# INV_OG5K_PW_V1.net
KiCad netlist of a schematic drawn in Altium Designer
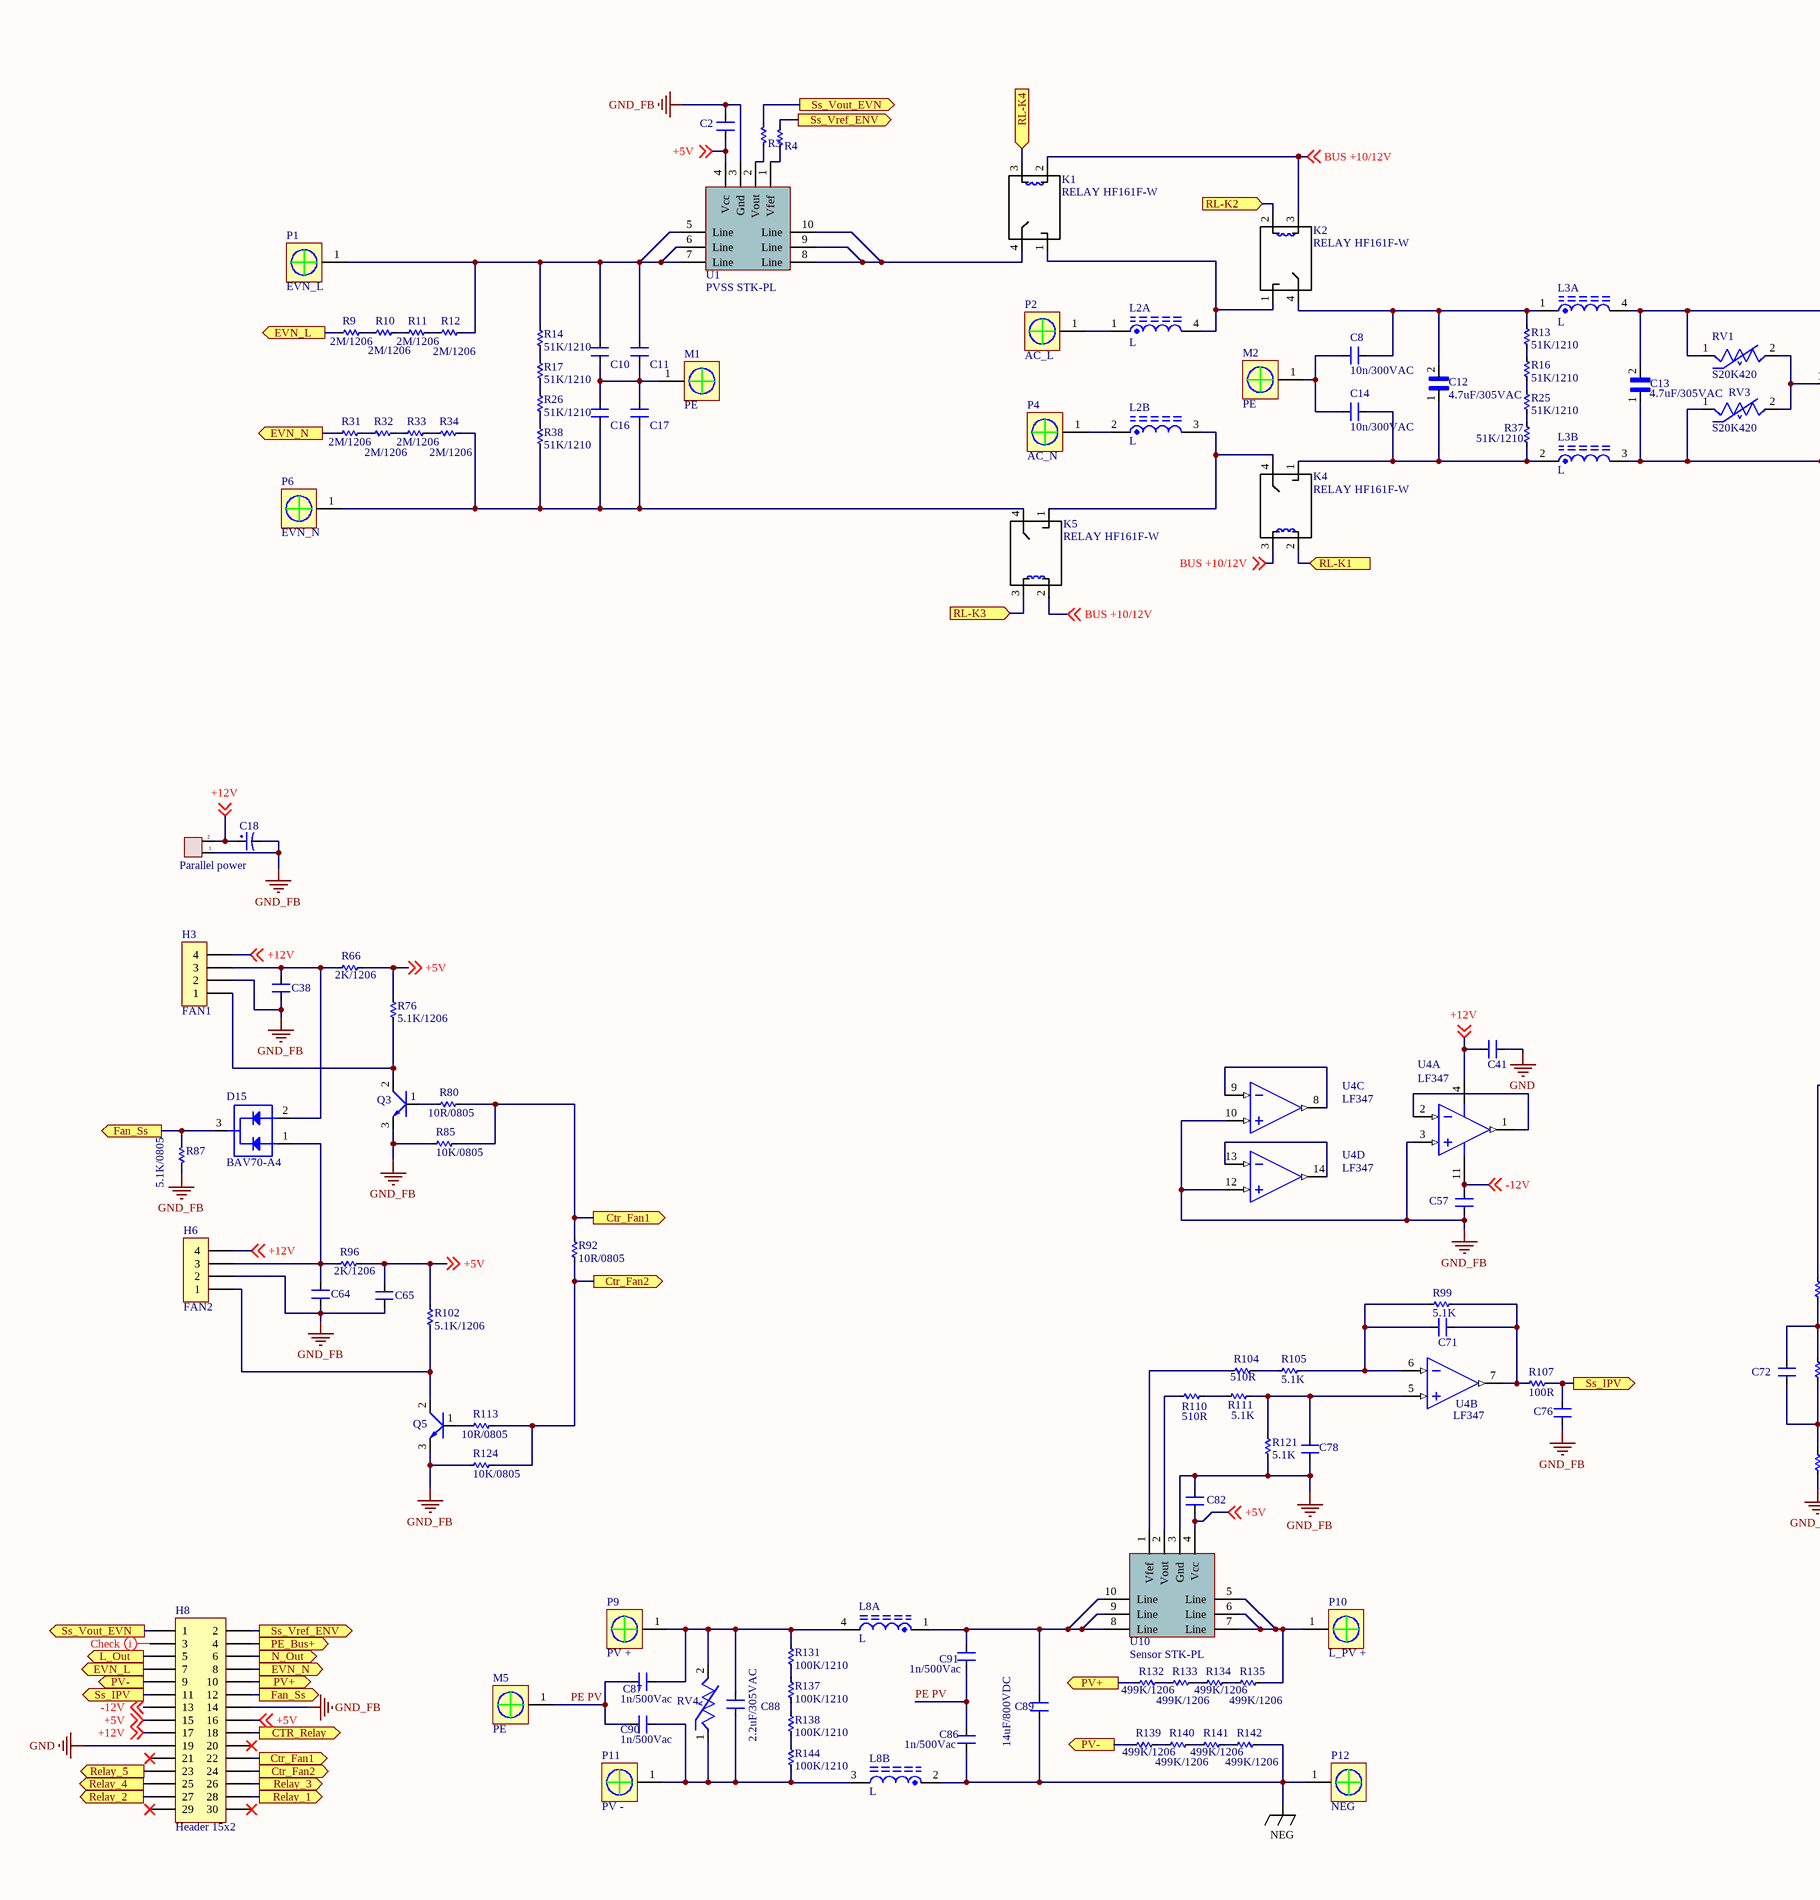
[diagram p0: INV.OG5K.PW.V1.SchDoc, left]
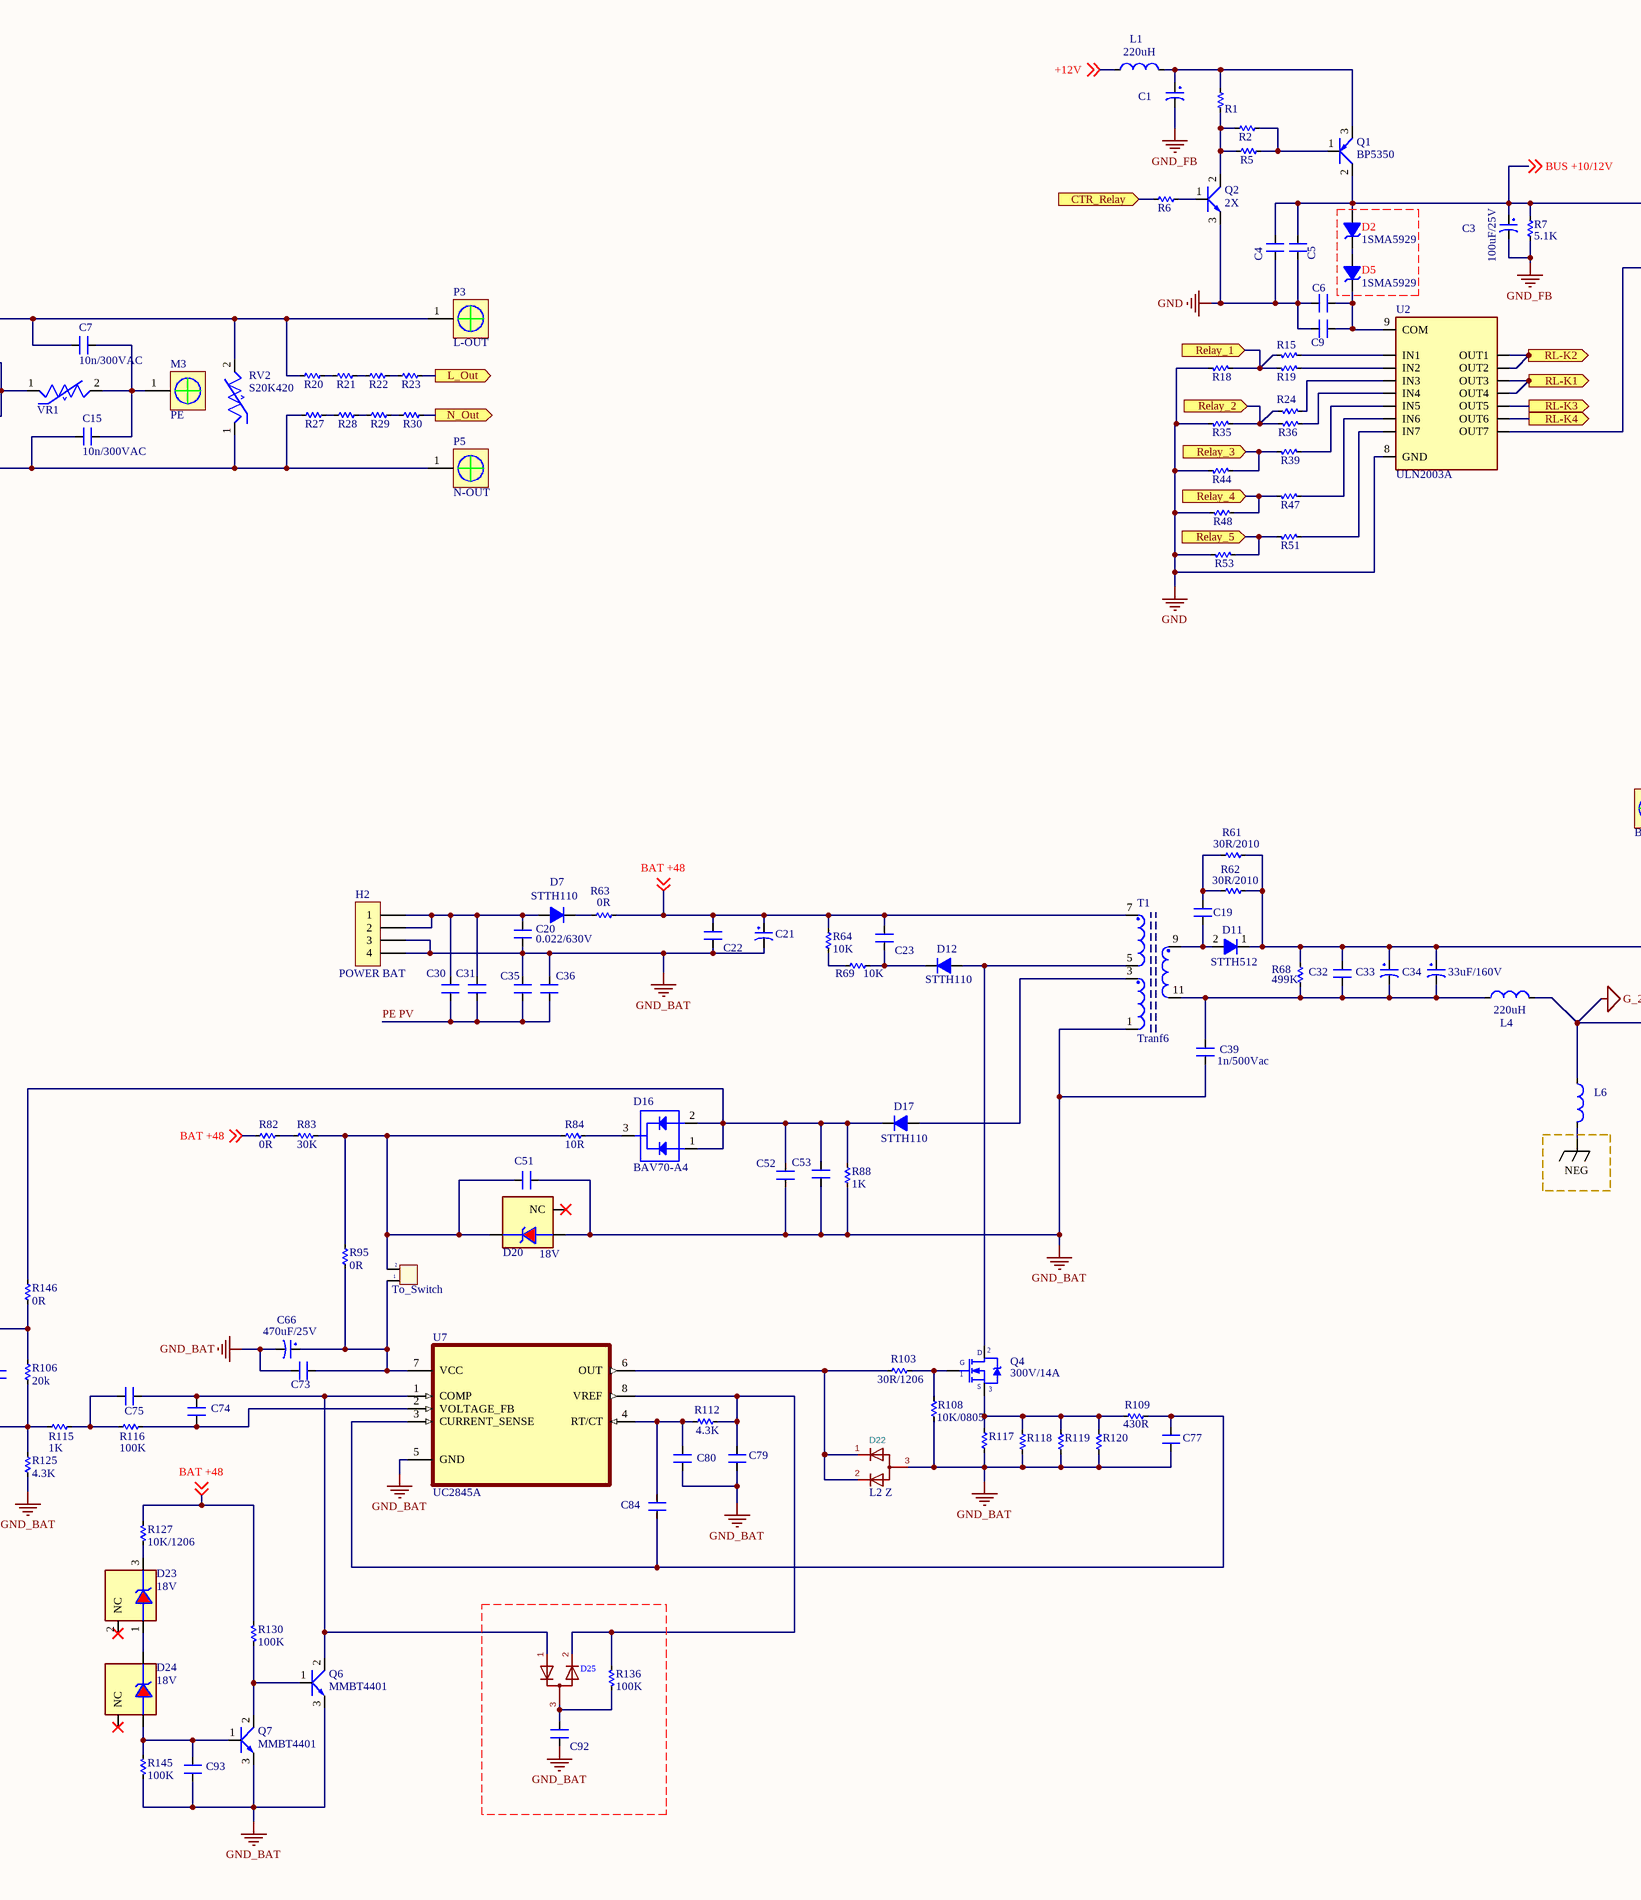
[diagram p1: INV.OG5K.PW.V1.SchDoc, middle]
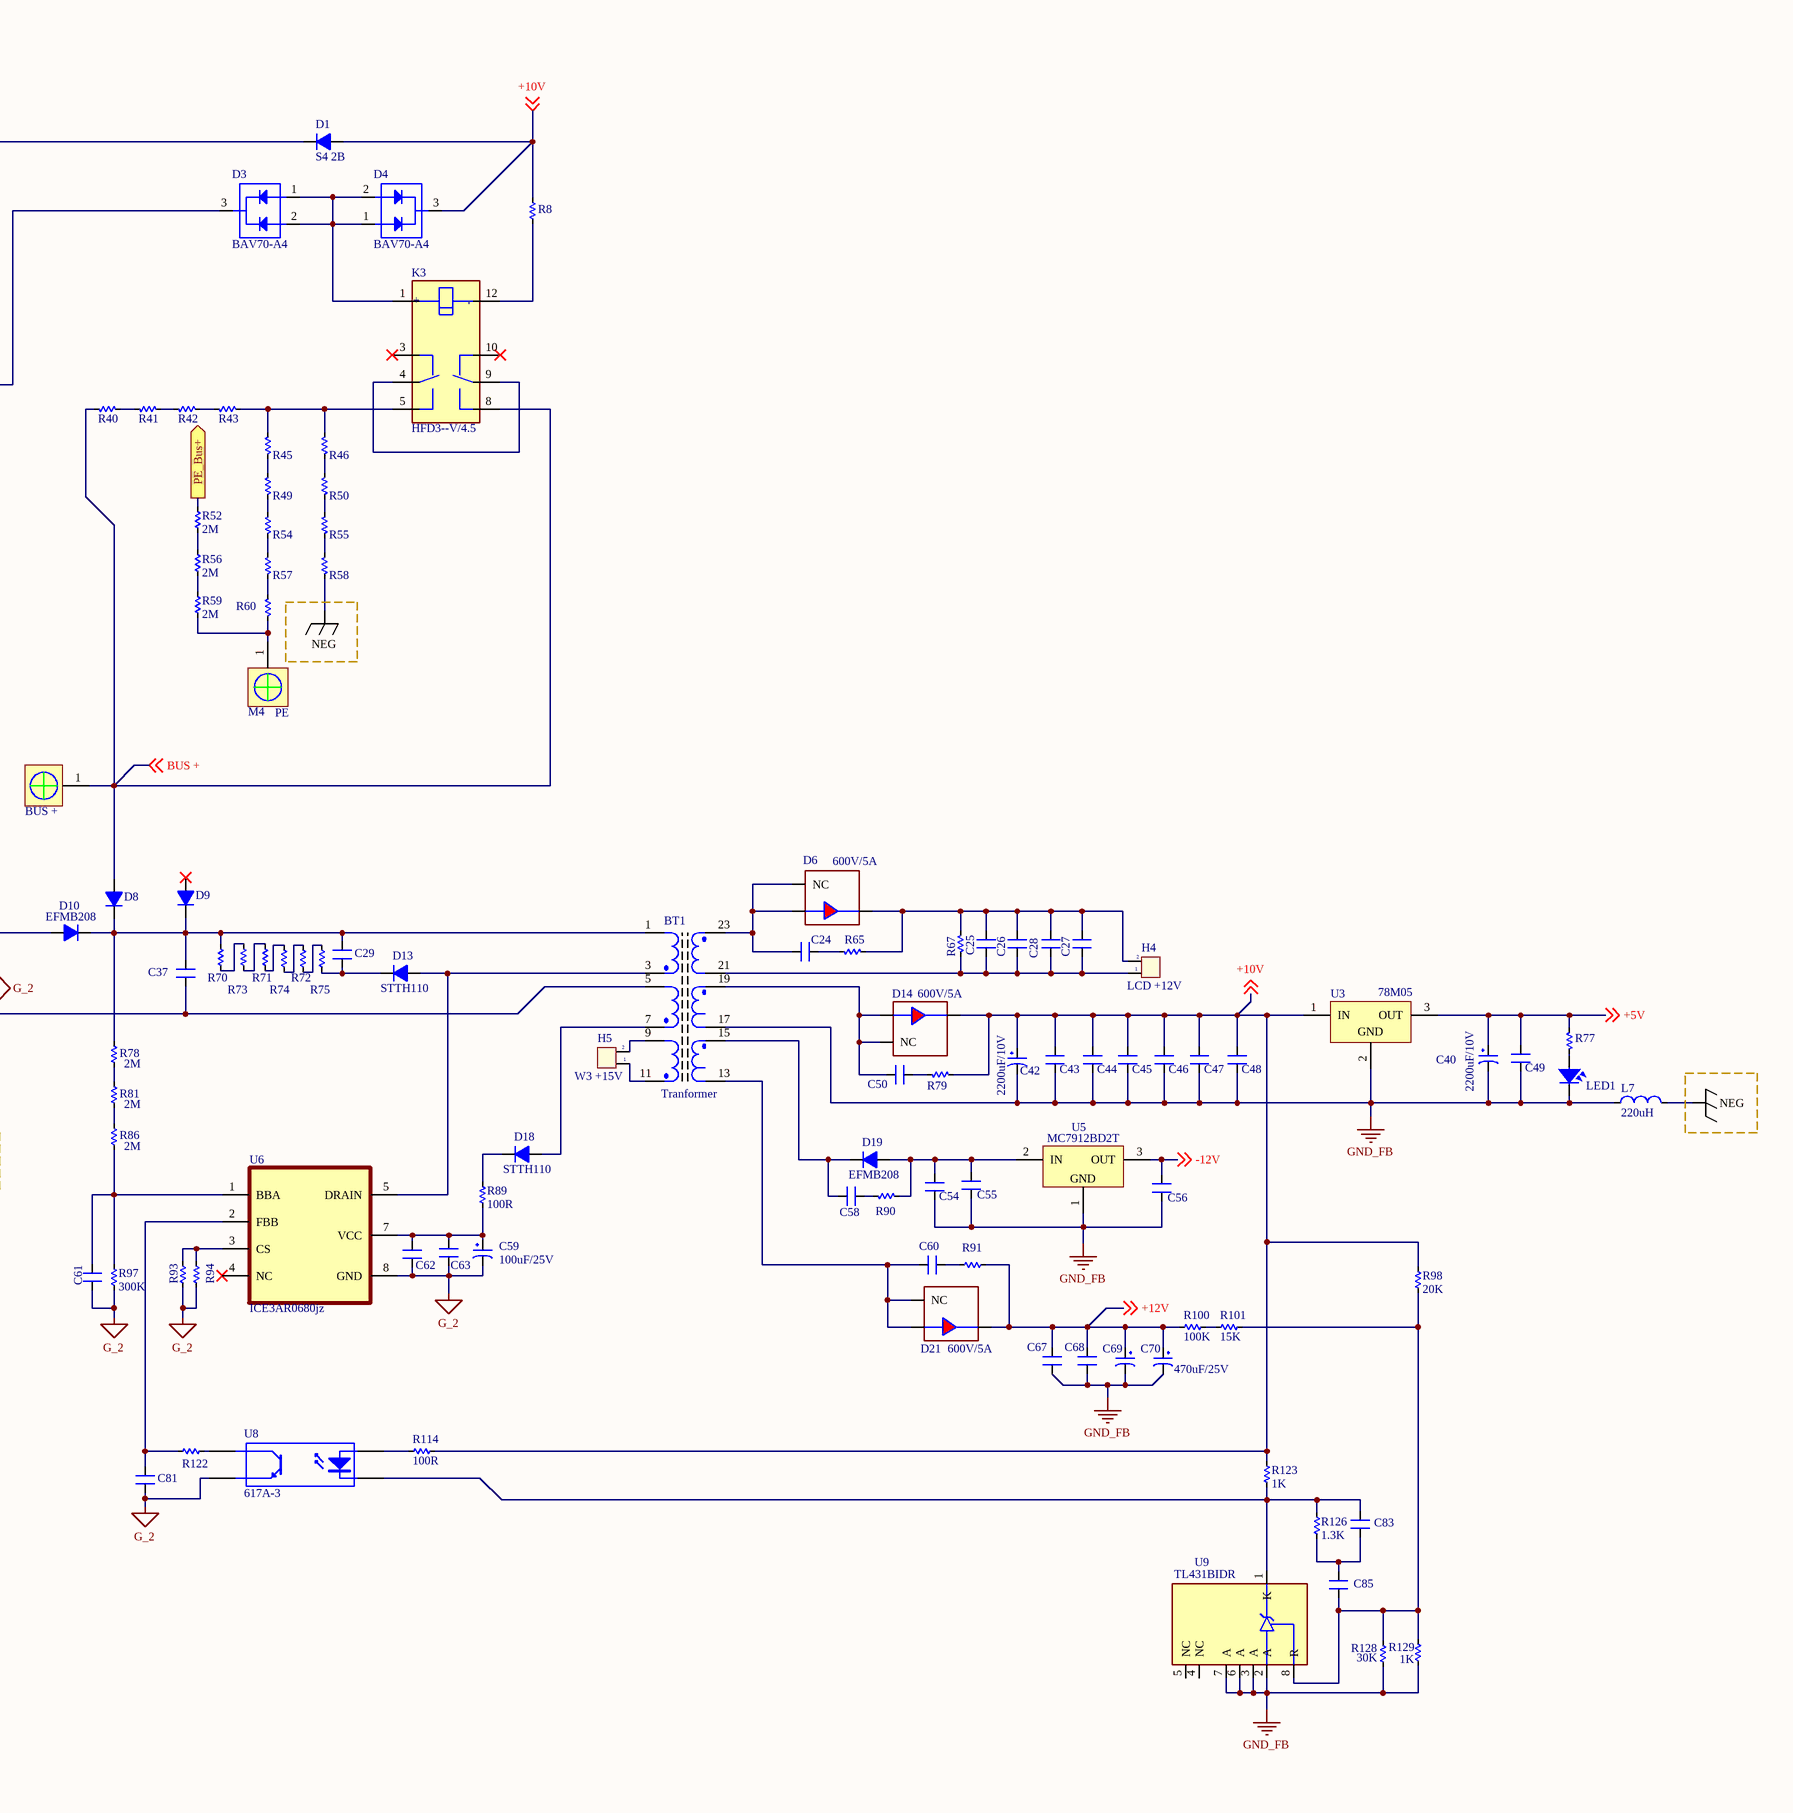
[diagram p2: INV.OG5K.PW.V1.SchDoc, right]

(export (version "E")
  (design (tool "Eeschema 10.0.6"))
  (components
    (comp (ref "BT1")
      (value "Tranformer")
      (footprint "Tranfomer 2-4")
      (description "Bien ap xung DVD")
      (fields (field (name "DESIGNED BY") "VanDungEvn"))
      (libsource (lib "Lib_RD_Cg") (part "Tranfomer 2-4"))
    )
    (comp (ref "C1")
      (value "100uF/25V")
      (footprint "CAP-TH_BD6.3-P2.50-D0.6-FD")
      (libsource (lib "") (part "Cap - 10x18 - N_1"))
    )
    (comp (ref "C2")
      (value "10n/300VAC")
      (footprint "CAP-SMD-0805 EX")
      (description "High Voltage Ceramic Capacitors CS103M")
      (libsource (lib "RAL") (part "CAP-SMD"))
    )
    (comp (ref "C3")
      (value "100uF/25V")
      (footprint "CAP-TH_BD6.3-P2.50-D0.6-FD")
      (libsource (lib "") (part "Cap - 10x18 - N_1"))
    )
    (comp (ref "C4") (value "~") (footprint "CAP-SMD-0805") (libsource (lib "RAL") (part "CAP-SMD")))
    (comp (ref "C5") (value "~") (footprint "CAP-SMD-0805") (libsource (lib "RAL") (part "CAP-SMD")))
    (comp (ref "C6") (value "~") (footprint "CAP-SMD-0805") (libsource (lib "RAL") (part "CAP-SMD")))
    (comp (ref "C7")
      (value "10n/300VAC")
      (footprint "Cap an toan CS103M")
      (description "High Voltage Ceramic Capacitors CS103M")
      (libsource (lib "RAL") (part "CAP-SMD"))
    )
    (comp (ref "C8")
      (value "10n/300VAC")
      (footprint "Cap an toan CS103M")
      (description "High Voltage Ceramic Capacitors CS103M")
      (libsource (lib "RAL") (part "CAP-SMD"))
    )
    (comp (ref "C9") (value "~") (footprint "CAP-SMD-0805") (libsource (lib "RAL") (part "CAP-SMD")))
    (comp (ref "C10")
      (value "10n/300VAC")
      (footprint "Cap an toan CS103M")
      (description "High Voltage Ceramic Capacitors CS103M")
      (libsource (lib "RAL") (part "CAP-SMD"))
    )
    (comp (ref "C11")
      (value "10n/300VAC")
      (footprint "Cap an toan CS103M")
      (description "High Voltage Ceramic Capacitors CS103M")
      (libsource (lib "RAL") (part "CAP-SMD"))
    )
    (comp (ref "C12")
      (value "4.7uF/305VAC")
      (footprint "CAP-TH_L31.5-W21.0-P27.50-D1.0")
      (description "Polypropylene Film Capacitor, 305V ac, ±20%, 4.7μF")
      (fields (field (name "MP") "ECWFG2J475KA") (field (name "MF") "Panasonic"))
      (libsource (lib "Lib_RD_Cg") (part "ECWFG2J475KA"))
    )
    (comp (ref "C13")
      (value "4.7uF/305VAC")
      (footprint "CAP-TH_L31.5-W21.0-P27.50-D1.0")
      (description "Polypropylene Film Capacitor, 305V ac, ±20%, 4.7μF")
      (fields (field (name "MP") "ECWFG2J475KA") (field (name "MF") "Panasonic"))
      (libsource (lib "Lib_RD_Cg") (part "ECWFG2J475KA"))
    )
    (comp (ref "C14")
      (value "10n/300VAC")
      (footprint "Cap an toan CS103M")
      (description "High Voltage Ceramic Capacitors CS103M")
      (libsource (lib "RAL") (part "CAP-SMD"))
    )
    (comp (ref "C15")
      (value "10n/300VAC")
      (footprint "Cap an toan CS103M")
      (description "High Voltage Ceramic Capacitors CS103M")
      (libsource (lib "RAL") (part "CAP-SMD"))
    )
    (comp (ref "C16")
      (value "10n/300VAC")
      (footprint "Cap an toan CS103M")
      (description "High Voltage Ceramic Capacitors CS103M")
      (libsource (lib "RAL") (part "CAP-SMD"))
    )
    (comp (ref "C17")
      (value "10n/300VAC")
      (footprint "Cap an toan CS103M")
      (description "High Voltage Ceramic Capacitors CS103M")
      (libsource (lib "RAL") (part "CAP-SMD"))
    )
    (comp (ref "C18")
      (value "470uF/25V")
      (footprint "CAP-TH_BD8.0-P3.50-D0.6-FD")
      (libsource (lib "") (part "Cap - 10x18 - N_2"))
    )
    (comp (ref "C19") (value "~") (footprint "CAP-SMD-1206") (libsource (lib "RAL") (part "CAP-SMD")))
    (comp (ref "C20")
      (value "0.022/630V")
      (footprint "CAP-TH_L10.5-W5.0-P7.50-D1.2")
      (description "WIMA MKS 4 Metallized Polyester (PET) Capacitors")
      (libsource (lib "RAL") (part "CAP-SMD"))
    )
    (comp (ref "C21")
      (value "27uF/100V")
      (footprint "CAP-TH_BD8.0-P3.50-D0.6-FD")
      (description "Cắm 100uF 25V")
      (libsource (lib "Lib_RD_Cg") (part "Cap - 10x18 - N"))
    )
    (comp (ref "C22") (value "~") (footprint "CAP-SMD-1206") (libsource (lib "RAL") (part "CAP-SMD")))
    (comp (ref "C23") (value "~") (footprint "CAP-SMD-1206") (libsource (lib "RAL") (part "CAP-SMD")))
    (comp (ref "C24") (value "~") (footprint "CAP-SMD-1206") (libsource (lib "RAL") (part "CAP-SMD")))
    (comp (ref "C25") (value "223J630V") (footprint "CAP-SMD-0805") (libsource (lib "RAL") (part "CAP-SMD")))
    (comp (ref "C26") (value "223J630V") (footprint "CAP-SMD-0805") (libsource (lib "RAL") (part "CAP-SMD")))
    (comp (ref "C27") (value "223J630V") (footprint "CAP-SMD-0805") (libsource (lib "RAL") (part "CAP-SMD")))
    (comp (ref "C28") (value "223J630V") (footprint "CAP-SMD-0805") (libsource (lib "RAL") (part "CAP-SMD")))
    (comp (ref "C29")
      (value "223J630V")
      (footprint "CAP-TH_L10.5-W5.0-P7.50-D1.2")
      (libsource (lib "RAL") (part "CAP-SMD"))
    )
    (comp (ref "C30")
      (value "~")
      (footprint "CAP-TH_L10.5-W5.0-P7.50-D1.2")
      (libsource (lib "RAL") (part "CAP-SMD"))
    )
    (comp (ref "C31")
      (value "~")
      (footprint "CAP-TH_L10.5-W5.0-P7.50-D1.2")
      (libsource (lib "RAL") (part "CAP-SMD"))
    )
    (comp (ref "C32") (value "~") (footprint "CAP-SMD-1206") (libsource (lib "RAL") (part "CAP-SMD")))
    (comp (ref "C33")
      (value "33uF/160V")
      (footprint "CAP-TH_BD13.0-P5.00-D0.6-FD")
      (libsource (lib "Lib_RD_Cg") (part "Cap - 10x18 - N"))
    )
    (comp (ref "C34")
      (value "33uF/160V")
      (footprint "CAP-TH_BD13.0-P5.00-D0.6-FD")
      (libsource (lib "Lib_RD_Cg") (part "Cap - 10x18 - N"))
    )
    (comp (ref "C35")
      (value "~")
      (footprint "CAP-TH_L10.5-W5.0-P7.50-D1.2")
      (libsource (lib "RAL") (part "CAP-SMD"))
    )
    (comp (ref "C36")
      (value "~")
      (footprint "CAP-TH_L10.5-W5.0-P7.50-D1.2")
      (libsource (lib "RAL") (part "CAP-SMD"))
    )
    (comp (ref "C37")
      (value "2uF/600VDC")
      (footprint "CAP DIP 31x12")
      (libsource (lib "RAL") (part "CAP-SMD"))
    )
    (comp (ref "C38") (value "~") (footprint "CAP-SMD-0805") (libsource (lib "RAL") (part "CAP-SMD")))
    (comp (ref "C39")
      (value "1n/500Vac")
      (footprint "CAP 1nF/500VAC, Y1")
      (libsource (lib "RAL") (part "CAP-SMD"))
    )
    (comp (ref "C40")
      (value "2200uF/10V")
      (footprint "CAP-TH_BD13.0-P5.00-D0.6-FD")
      (libsource (lib "Lib_RD_Cg") (part "Cap - 10x18 - N"))
    )
    (comp (ref "C41") (value "~") (footprint "CAP-SMD-0805") (libsource (lib "RAL") (part "CAP-SMD")))
    (comp (ref "C42")
      (value "2200uF/10V")
      (footprint "CAP-TH_BD13.0-P5.00-D0.6-FD")
      (libsource (lib "Lib_RD_Cg") (part "Cap - 10x18 - N"))
    )
    (comp (ref "C43") (value "~") (footprint "CAP-SMD-0805") (libsource (lib "RAL") (part "CAP-SMD")))
    (comp (ref "C44") (value "~") (footprint "CAP-SMD-0805") (libsource (lib "RAL") (part "CAP-SMD")))
    (comp (ref "C45") (value "~") (footprint "CAP-SMD-0805") (libsource (lib "RAL") (part "CAP-SMD")))
    (comp (ref "C46") (value "~") (footprint "CAP-SMD-0805") (libsource (lib "RAL") (part "CAP-SMD")))
    (comp (ref "C47") (value "~") (footprint "CAP-SMD-0805") (libsource (lib "RAL") (part "CAP-SMD")))
    (comp (ref "C48") (value "~") (footprint "CAP-SMD-0805") (libsource (lib "RAL") (part "CAP-SMD")))
    (comp (ref "C49") (value "~") (footprint "CAP-SMD-0805") (libsource (lib "RAL") (part "CAP-SMD")))
    (comp (ref "C50") (value "~") (footprint "CAP-SMD-1206") (libsource (lib "RAL") (part "CAP-SMD")))
    (comp (ref "C51") (value "~") (footprint "CAP-SMD-0805") (libsource (lib "RAL") (part "CAP-SMD")))
    (comp (ref "C52") (value "~") (footprint "CAP-SMD-0805") (libsource (lib "RAL") (part "CAP-SMD")))
    (comp (ref "C53") (value "~") (footprint "CAP-SMD-0805") (libsource (lib "RAL") (part "CAP-SMD")))
    (comp (ref "C54") (value "~") (footprint "CAP-SMD-0805") (libsource (lib "RAL") (part "CAP-SMD")))
    (comp (ref "C55") (value "~") (footprint "CAP-SMD-0805") (libsource (lib "RAL") (part "CAP-SMD")))
    (comp (ref "C56") (value "~") (footprint "CAP-SMD-0805") (libsource (lib "RAL") (part "CAP-SMD")))
    (comp (ref "C57") (value "~") (footprint "CAP-SMD-0805") (libsource (lib "RAL") (part "CAP-SMD")))
    (comp (ref "C58") (value "~") (footprint "CAP-SMD-1206") (libsource (lib "RAL") (part "CAP-SMD")))
    (comp (ref "C59")
      (value "100uF/25V")
      (footprint "CAP-TH_BD6.3-P2.50-D0.6-FD")
      (description "Cắm 100uF 25V")
      (libsource (lib "Lib_RD_Cg") (part "Cap - 10x18 - N"))
    )
    (comp (ref "C60") (value "~") (footprint "CAP-SMD-1206") (libsource (lib "RAL") (part "CAP-SMD")))
    (comp (ref "C61") (value "~") (footprint "CAP-SMD-0805") (libsource (lib "RAL") (part "CAP-SMD")))
    (comp (ref "C62") (value "223J630V") (footprint "CAP-SMD-0805") (libsource (lib "RAL") (part "CAP-SMD")))
    (comp (ref "C63") (value "223J630V") (footprint "CAP-SMD-0805") (libsource (lib "RAL") (part "CAP-SMD")))
    (comp (ref "C64") (value "~") (footprint "CAP-SMD-0805") (libsource (lib "RAL") (part "CAP-SMD")))
    (comp (ref "C65") (value "~") (footprint "CAP-SMD-0805") (libsource (lib "RAL") (part "CAP-SMD")))
    (comp (ref "C66")
      (value "470uF/25V")
      (footprint "CAP-TH_BD8.0-P3.50-D0.6-FD")
      (description "Cắm 100uF 25V")
      (libsource (lib "") (part "Cap - 10x18 - N_3"))
    )
    (comp (ref "C67") (value "~") (footprint "CAP-SMD-0805") (libsource (lib "RAL") (part "CAP-SMD")))
    (comp (ref "C68") (value "~") (footprint "CAP-SMD-0805") (libsource (lib "RAL") (part "CAP-SMD")))
    (comp (ref "C69")
      (value "470uF/25V")
      (footprint "CAP-TH_BD8.0-P3.50-D0.6-FD")
      (libsource (lib "") (part "Cap - 10x18 - N_1"))
    )
    (comp (ref "C70")
      (value "470uF/25V")
      (footprint "CAP-TH_BD8.0-P3.50-D0.6-FD")
      (libsource (lib "") (part "Cap - 10x18 - N_1"))
    )
    (comp (ref "C71") (value "~") (footprint "CAP-SMD-0805") (libsource (lib "RAL") (part "CAP-SMD")))
    (comp (ref "C72") (value "~") (footprint "CAP-SMD-0805") (libsource (lib "RAL") (part "CAP-SMD")))
    (comp (ref "C73") (value "~") (footprint "CAP-SMD-0805") (libsource (lib "RAL") (part "CAP-SMD")))
    (comp (ref "C74") (value "~") (footprint "CAP-SMD-0805") (libsource (lib "RAL") (part "CAP-SMD")))
    (comp (ref "C75") (value "~") (footprint "CAP-SMD-0805") (libsource (lib "RAL") (part "CAP-SMD")))
    (comp (ref "C76") (value "~") (footprint "CAP-SMD-0805") (libsource (lib "RAL") (part "CAP-SMD")))
    (comp (ref "C77") (value "~") (footprint "CAP-SMD-0805") (libsource (lib "RAL") (part "CAP-SMD")))
    (comp (ref "C78") (value "~") (footprint "CAP-SMD-0805") (libsource (lib "RAL") (part "CAP-SMD")))
    (comp (ref "C79") (value "~") (footprint "CAP-SMD-0805") (libsource (lib "RAL") (part "CAP-SMD")))
    (comp (ref "C80") (value "~") (footprint "CAP-SMD-0805") (libsource (lib "RAL") (part "CAP-SMD")))
    (comp (ref "C81") (value "~") (footprint "CAP-SMD-0805") (libsource (lib "RAL") (part "CAP-SMD")))
    (comp (ref "C82") (value "~") (footprint "CAP-SMD-0805 EX") (libsource (lib "RAL") (part "CAP-SMD")))
    (comp (ref "C83") (value "~") (footprint "CAP-SMD-0805") (libsource (lib "RAL") (part "CAP-SMD")))
    (comp (ref "C84") (value "~") (footprint "CAP-SMD-0805") (libsource (lib "RAL") (part "CAP-SMD")))
    (comp (ref "C85") (value "~") (footprint "CAP-SMD-0805") (libsource (lib "RAL") (part "CAP-SMD")))
    (comp (ref "C86")
      (value "1n/500Vac")
      (footprint "CAP 1nF/500VAC, Y1")
      (libsource (lib "RAL") (part "CAP-SMD"))
    )
    (comp (ref "C87")
      (value "1n/500Vac")
      (footprint "CAP 1nF/500VAC, Y1")
      (libsource (lib "RAL") (part "CAP-SMD"))
    )
    (comp (ref "C88")
      (value "2.2uF/305VAC")
      (footprint "CAP-TH_L26.5-W14.5-P22.50-D1.2")
      (libsource (lib "RAL") (part "CAP-SMD"))
    )
    (comp (ref "C89")
      (value "14uF/800VDC")
      (footprint "CAP DIP 42x18")
      (libsource (lib "RAL") (part "CAP-SMD"))
    )
    (comp (ref "C90")
      (value "1n/500Vac")
      (footprint "CAP 1nF/500VAC, Y1")
      (libsource (lib "RAL") (part "CAP-SMD"))
    )
    (comp (ref "C91")
      (value "1n/500Vac")
      (footprint "CAP 1nF/500VAC, Y1")
      (libsource (lib "RAL") (part "CAP-SMD"))
    )
    (comp (ref "C92") (value "~") (footprint "CAP-SMD-0805") (libsource (lib "RAL") (part "CAP-SMD")))
    (comp (ref "C93") (value "~") (footprint "CAP-SMD-0805") (libsource (lib "RAL") (part "CAP-SMD")))
    (comp (ref "D1") (value "S4 2B") (footprint "SMB") (libsource (lib "Lib_RD_Cg") (part "DIODE")))
    (comp (ref "D2")
      (value "1SMA5929")
      (footprint "SMA")
      (description "Diode Zenner 15V")
      (libsource (lib "Lib_RD_Cg") (part "DIODE ZENNER"))
    )
    (comp (ref "D3")
      (value "BAV70-A4")
      (footprint "SOT23-132")
      (fields (field (name "MP") "STTH2003CG-TR"))
      (libsource (lib "Lib_RD_Cg") (part "Diode Double"))
    )
    (comp (ref "D4")
      (value "BAV70-A4")
      (footprint "SOT23-132")
      (fields (field (name "MP") "STTH2003CG-TR"))
      (libsource (lib "Lib_RD_Cg") (part "Diode Double"))
    )
    (comp (ref "D5")
      (value "1SMA5929")
      (footprint "SMA")
      (description "Diode Zenner 15V")
      (libsource (lib "Lib_RD_Cg") (part "DIODE ZENNER"))
    )
    (comp (ref "D6")
      (value "600V/5A")
      (footprint "TO252-132")
      (description "600V/5A Diode SHHT 506B")
      (fields (field (name "MF") "ON Semiconductor") (field (name "MP") "BZX84-C7V5"))
      (libsource (lib "") (part "Diode SHHT 506B_1"))
    )
    (comp (ref "D7")
      (value "STTH110")
      (footprint "SMA")
      (description "Diode 1000V/1A SMB")
      (libsource (lib "Lib_RD_Cg") (part "DIODE"))
    )
    (comp (ref "D8")
      (value "EFMB208")
      (footprint "SMB")
      (description "Diode 600V/2A SMB thay the ES2J")
      (libsource (lib "Lib_RD_Cg") (part "DIODE"))
    )
    (comp (ref "D9")
      (value "EFMB208")
      (footprint "SMB")
      (description "Diode 600V/2A SMB thay the ES2J")
      (libsource (lib "Lib_RD_Cg") (part "DIODE"))
    )
    (comp (ref "D10")
      (value "EFMB208")
      (footprint "SMB")
      (description "Diode 600V/2A SMB thay the ES2J")
      (libsource (lib "Lib_RD_Cg") (part "DIODE"))
    )
    (comp (ref "D11")
      (value "STTH512")
      (footprint "TO220 - DIP 2 Pin Heatsink")
      (description "Diode 1200V/5A")
      (libsource (lib "") (part "DIODE_1"))
    )
    (comp (ref "D12")
      (value "STTH110")
      (footprint "SMA")
      (description "Diode 1000V/1A SMB")
      (libsource (lib "Lib_RD_Cg") (part "DIODE"))
    )
    (comp (ref "D13")
      (value "STTH110")
      (footprint "SMA")
      (description "Diode 1000V/1A SMB")
      (libsource (lib "Lib_RD_Cg") (part "DIODE"))
    )
    (comp (ref "D14")
      (value "600V/5A")
      (footprint "TO252-132")
      (description "600V/5A Diode SHHT 506B")
      (fields (field (name "MF") "ON Semiconductor") (field (name "MP") "BZX84-C7V5"))
      (libsource (lib "Lib_RD_Cg") (part "Diode SHHT 506B"))
    )
    (comp (ref "D15")
      (value "BAV70-A4")
      (footprint "SOT23-132")
      (fields (field (name "MP") "STTH2003CG-TR"))
      (libsource (lib "Lib_RD_Cg") (part "Diode Double"))
    )
    (comp (ref "D16")
      (value "BAV70-A4")
      (footprint "SOT23-132")
      (fields (field (name "MP") "STTH2003CG-TR"))
      (libsource (lib "Lib_RD_Cg") (part "Diode Double"))
    )
    (comp (ref "D17")
      (value "STTH110")
      (footprint "SMA")
      (description "Diode 1000V/1A SMB")
      (libsource (lib "Lib_RD_Cg") (part "DIODE"))
    )
    (comp (ref "D18")
      (value "STTH110")
      (footprint "SMB")
      (description "Diode 1000V/1A SMB")
      (libsource (lib "Lib_RD_Cg") (part "DIODE"))
    )
    (comp (ref "D19")
      (value "EFMB208")
      (footprint "SMB")
      (description "Diode 600V/2A SMB thay the ES2J")
      (libsource (lib "Lib_RD_Cg") (part "DIODE"))
    )
    (comp (ref "D20")
      (value "18V")
      (footprint "SOT23-132")
      (description "BZX84-C18(Y6W) Zenner 18V thay the BZT52C18")
      (fields (field (name "MF") "ON Semiconductor") (field (name "MP") "BZX84-C7V5"))
      (libsource (lib "") (part "Diode Zener Sot-95_2"))
    )
    (comp (ref "D21")
      (value "600V/5A")
      (footprint "TO252-132")
      (description "600V/5A Diode SHHT 506B")
      (fields (field (name "MF") "ON Semiconductor") (field (name "MP") "BZX84-C7V5"))
      (libsource (lib "") (part "Diode SHHT 506B_1"))
    )
    (comp (ref "D22")
      (value "L2 Z")
      (footprint "SOT23-132")
      (description "LBAS40-06LT1G\r\n S-LBAS40-06LT1G")
      (libsource (lib "Lib_RD_Cg") (part "Dual-Diode_CA"))
    )
    (comp (ref "D23")
      (value "18V")
      (footprint "SOT23-132")
      (description "BZX84-C18(Y6W) Zenner 18V thay the BZT52C18")
      (fields (field (name "MF") "ON Semiconductor") (field (name "MP") "BZX84-C7V5"))
      (libsource (lib "Lib_RD_Cg") (part "Diode Zener Sot-95"))
    )
    (comp (ref "D24")
      (value "18V")
      (footprint "SOT23-132")
      (description "BZX84-C18(Y6W) Zenner 18V thay the BZT52C18")
      (fields (field (name "MF") "ON Semiconductor") (field (name "MP") "BZX84-C7V5"))
      (libsource (lib "") (part "Diode Zener Sot-95_1"))
    )
    (comp (ref "D25")
      (value "Dual-Diode_CA_1")
      (footprint "SOT23-132")
      (description "BAT54S(D88) thay the BAV99:A7")
      (libsource (lib "Lib_RD_Cg") (part "Dual-Diode_CA_1"))
    )
    (comp (ref "H1") (value "Parallel power") (footprint "Header2") (libsource (lib "") (part "Jump2_1")))
    (comp (ref "H2")
      (value "POWER BAT")
      (footprint "Header4")
      (description "Cắm")
      (libsource (lib "") (part "Header 4P 2.54 Duc Thang_1"))
    )
    (comp (ref "H3")
      (value "FAN1")
      (footprint "Header4")
      (description "Cắm")
      (libsource (lib "Altium_Lib_by_KhueNguyenCreator") (part "Header 4P 2.54 Duc Thang"))
    )
    (comp (ref "H4") (value "LCD +12V") (footprint "Header2") (libsource (lib "AE_RD") (part "Jump2")))
    (comp (ref "H5") (value "W3 +15V") (footprint "Header2") (libsource (lib "") (part "Jump2_1")))
    (comp (ref "H6")
      (value "FAN2")
      (footprint "Header4")
      (description "Cắm")
      (libsource (lib "Altium_Lib_by_KhueNguyenCreator") (part "Header 4P 2.54 Duc Thang"))
    )
    (comp (ref "H7") (value "To_Switch") (footprint "Header2") (libsource (lib "AE_RD") (part "Jump2")))
    (comp (ref "H8")
      (value "Header 15x2")
      (footprint "Header 2x15 V2")
      (description "Header, 15x2-Pin 2.5mm")
      (fields (field (name "PUBLISHER") "Altium Limited"))
      (libsource (lib "Lib_RD_Cg") (part "Header 15x2"))
    )
    (comp (ref "K1")
      (value "RELAY HF161F-W")
      (footprint "RELAY HF161F-W")
      (description "RELAY HF161F-W 277V/26A")
      (libsource (lib "") (part "RELAY 10A/250V-SY_1"))
    )
    (comp (ref "K2")
      (value "RELAY HF161F-W")
      (footprint "RELAY HF161F-W")
      (description "RELAY HF161F-W 277V/26A")
      (libsource (lib "Lib_RD_Cg") (part "RELAY 10A/250V-SY"))
    )
    (comp (ref "K3")
      (value "HFD3--V/4.5")
      (footprint "RELAY 3/5-1")
      (fields (field (name "MF") "Hongfa") (field (name "MP") "HFD3/012-L2"))
      (libsource (lib "Lib_RD_Cg") (part "HFD3--V/4.5"))
    )
    (comp (ref "K4")
      (value "RELAY HF161F-W")
      (footprint "RELAY HF161F-W")
      (description "RELAY HF161F-W 277V/26A")
      (libsource (lib "Lib_RD_Cg") (part "RELAY 10A/250V-SY"))
    )
    (comp (ref "K5")
      (value "RELAY HF161F-W")
      (footprint "RELAY HF161F-W")
      (description "RELAY HF161F-W 277V/26A")
      (libsource (lib "Lib_RD_Cg") (part "RELAY 10A/250V-SY"))
    )
    (comp (ref "L1")
      (value "220uH")
      (footprint "IND-SMD_L10.2-W10.0_MS104R")
      (description "Inductor")
      (libsource (lib "Lib_RD_Cg") (part "L1"))
    )
    (comp (ref "L2")
      (value "L")
      (footprint "LAC2OG5K-V1")
      (description "Cuon cam AC")
      (fields (field (name "DESIGNED BY") "VanDungEvn"))
      (libsource (lib "") (part "LAC2OG5K-V1_1"))
    )
    (comp (ref "L3")
      (value "L")
      (footprint "LAC1OG5K-V1")
      (description "Cuon cam AC")
      (fields (field (name "DESIGNED BY") "VanDungEvn"))
      (libsource (lib "") (part "LAC1OG5K-V1_1"))
    )
    (comp (ref "L4")
      (value "220uH")
      (footprint "IND-SMD_L10.2-W10.0_MS104R")
      (description "Inductor")
      (libsource (lib "Lib_RD_Cg") (part "L1"))
    )
    (comp (ref "L6")
      (value "~")
      (footprint "IND-SMD_L10.2-W10.0_MS104R")
      (description "Inductor")
      (libsource (lib "") (part "L1_1"))
    )
    (comp (ref "L7")
      (value "220uH")
      (footprint "IND-SMD_L10.2-W10.0_MS104R")
      (description "Inductor")
      (libsource (lib "Lib_RD_Cg") (part "L1"))
    )
    (comp (ref "L8")
      (value "L")
      (footprint "LPVOG5K-V1")
      (fields (field (name "DESIGNED BY") "VanDungEvn"))
      (libsource (lib "") (part "LPVOG5K-V1_1"))
    )
    (comp (ref "LED1") (value "LED") (footprint "LED-0805-Blue") (libsource (lib "RAL") (part "LED1-SMD")))
    (comp (ref "M1") (value "PE") (footprint "COPER") (libsource (lib "") (part "Copper_3")))
    (comp (ref "M2") (value "PE") (footprint "COPER") (libsource (lib "Lib_RD_Cg") (part "Copper")))
    (comp (ref "M3") (value "PE") (footprint "COPER") (libsource (lib "") (part "Copper_1")))
    (comp (ref "M4") (value "PE") (footprint "COPER") (libsource (lib "") (part "Copper_2")))
    (comp (ref "M5") (value "PE") (footprint "COPER") (libsource (lib "Lib_RD_Cg") (part "Copper")))
    (comp (ref "P1") (value "EVN_L") (footprint "Copper Pipe 4 DIP") (libsource (lib "") (part "Copper_2")))
    (comp (ref "P2")
      (value "AC_L")
      (footprint "Copper Pipe 4 DIP")
      (libsource (lib "Lib_RD_Cg") (part "Copper"))
    )
    (comp (ref "P3") (value "L-OUT") (footprint "Copper Pipe 4 DIP") (libsource (lib "") (part "Copper_1")))
    (comp (ref "P4")
      (value "AC_N")
      (footprint "Copper Pipe 4 DIP")
      (libsource (lib "Lib_RD_Cg") (part "Copper"))
    )
    (comp (ref "P5") (value "N-OUT") (footprint "Copper Pipe 4 DIP") (libsource (lib "") (part "Copper_1")))
    (comp (ref "P6") (value "EVN_N") (footprint "Copper Pipe 4 DIP") (libsource (lib "") (part "Copper_2")))
    (comp (ref "P8")
      (value "BUS +")
      (footprint "Copper Pipe 4 DIP")
      (libsource (lib "Lib_RD_Cg") (part "Copper"))
    )
    (comp (ref "P9")
      (value "PV +")
      (footprint "Copper Pipe 4 DIP")
      (libsource (lib "Lib_RD_Cg") (part "Copper"))
    )
    (comp (ref "P10") (value "L_PV +") (footprint "Copper Pipe 4 DIP") (libsource (lib "") (part "Copper_3")))
    (comp (ref "P11")
      (value "PV -")
      (footprint "Copper Pipe 4 DIP")
      (libsource (lib "Lib_RD_Cg") (part "Copper"))
    )
    (comp (ref "P12") (value "NEG") (footprint "Copper Pipe 4 DIP") (libsource (lib "") (part "Copper_3")))
    (comp (ref "Q1")
      (value "BP5350")
      (footprint "SOT223")
      (description "thay the B772")
      (libsource (lib "Lib_RD_Cg") (part "B772M-PNP"))
    )
    (comp (ref "Q2")
      (value "2X")
      (footprint "SOT23-123")
      (description "thay the MMPT2222 40V/06A")
      (libsource (lib "Lib_RD_Cg") (part "D882M"))
    )
    (comp (ref "Q3") (value "~") (footprint "SOT23-123") (libsource (lib "Lib_RD_Cg") (part "D882M")))
    (comp (ref "Q4")
      (value "300V/14A")
      (footprint "TO263_123")
      (description "14N30")
      (libsource (lib "RAL") (part "MOSFET IRF N"))
    )
    (comp (ref "Q5") (value "~") (footprint "SOT23-123") (libsource (lib "Lib_RD_Cg") (part "D882M")))
    (comp (ref "Q6")
      (value "MMBT4401")
      (footprint "SOT23-123")
      (description "NPN")
      (libsource (lib "Lib_RD_Cg") (part "D882M"))
    )
    (comp (ref "Q7")
      (value "MMBT4401")
      (footprint "SOT23-123")
      (description "NPN")
      (libsource (lib "Lib_RD_Cg") (part "D882M"))
    )
    (comp (ref "R1")
      (value "10K")
      (footprint "RES-SMD-0805")
      (description "Resistor")
      (fields
        (field (name "MANUFACTURER") "Generic Components")
        (field (name "PUBLISHER") "Altium Hobart Technology Centre")
      )
      (libsource (lib "RAL") (part "Res-SMD"))
    )
    (comp (ref "R2")
      (value "2K")
      (footprint "RES-SMD-0805")
      (description "Resistor")
      (fields
        (field (name "MANUFACTURER") "Generic Components")
        (field (name "PUBLISHER") "Altium Hobart Technology Centre")
      )
      (libsource (lib "RAL") (part "Res-SMD"))
    )
    (comp (ref "R3")
      (value "1K/0603")
      (footprint "RES-SMD-0603 EX")
      (description "Resistor")
      (fields
        (field (name "MANUFACTURER") "Generic Components")
        (field (name "PUBLISHER") "Altium Hobart Technology Centre")
      )
      (libsource (lib "RAL") (part "Res-SMD"))
    )
    (comp (ref "R4")
      (value "1K/0603")
      (footprint "RES-SMD-0603 EX")
      (description "Resistor")
      (fields
        (field (name "MANUFACTURER") "Generic Components")
        (field (name "PUBLISHER") "Altium Hobart Technology Centre")
      )
      (libsource (lib "RAL") (part "Res-SMD"))
    )
    (comp (ref "R5")
      (value "2K")
      (footprint "RES-SMD-0805")
      (description "Resistor")
      (fields
        (field (name "MANUFACTURER") "Generic Components")
        (field (name "PUBLISHER") "Altium Hobart Technology Centre")
      )
      (libsource (lib "RAL") (part "Res-SMD"))
    )
    (comp (ref "R6")
      (value "20K")
      (footprint "RES-SMD-0805")
      (description "Resistor")
      (fields
        (field (name "MANUFACTURER") "Generic Components")
        (field (name "PUBLISHER") "Altium Hobart Technology Centre")
      )
      (libsource (lib "RAL") (part "Res-SMD"))
    )
    (comp (ref "R7")
      (value "5.1K")
      (footprint "RES-SMD-0805")
      (description "Resistor")
      (fields
        (field (name "MANUFACTURER") "Generic Components")
        (field (name "PUBLISHER") "Altium Hobart Technology Centre")
      )
      (libsource (lib "RAL") (part "Res-SMD"))
    )
    (comp (ref "R8")
      (value "51R")
      (footprint "RES-SMD-0805")
      (description "Resistor")
      (fields
        (field (name "MANUFACTURER") "Generic Components")
        (field (name "PUBLISHER") "Altium Hobart Technology Centre")
      )
      (libsource (lib "RAL") (part "Res-SMD"))
    )
    (comp (ref "R9")
      (value "2M/1206")
      (footprint "RES-SMD-1206")
      (description "Resistor")
      (fields
        (field (name "MANUFACTURER") "Generic Components")
        (field (name "PUBLISHER") "Altium Hobart Technology Centre")
      )
      (libsource (lib "RAL") (part "Res-SMD"))
    )
    (comp (ref "R10")
      (value "2M/1206")
      (footprint "RES-SMD-1206")
      (description "Resistor")
      (fields
        (field (name "MANUFACTURER") "Generic Components")
        (field (name "PUBLISHER") "Altium Hobart Technology Centre")
      )
      (libsource (lib "RAL") (part "Res-SMD"))
    )
    (comp (ref "R11")
      (value "2M/1206")
      (footprint "RES-SMD-1206")
      (description "Resistor")
      (fields
        (field (name "MANUFACTURER") "Generic Components")
        (field (name "PUBLISHER") "Altium Hobart Technology Centre")
      )
      (libsource (lib "RAL") (part "Res-SMD"))
    )
    (comp (ref "R12")
      (value "2M/1206")
      (footprint "RES-SMD-1206")
      (description "Resistor")
      (fields
        (field (name "MANUFACTURER") "Generic Components")
        (field (name "PUBLISHER") "Altium Hobart Technology Centre")
      )
      (libsource (lib "RAL") (part "Res-SMD"))
    )
    (comp (ref "R13")
      (value "51K/1210")
      (footprint "RES-SMD-1210 EX")
      (description "Resistor")
      (fields
        (field (name "MANUFACTURER") "Generic Components")
        (field (name "PUBLISHER") "Altium Hobart Technology Centre")
      )
      (libsource (lib "RAL") (part "Res-SMD"))
    )
    (comp (ref "R14")
      (value "51K/1210")
      (footprint "RES-SMD-1210 EX")
      (description "Resistor")
      (fields
        (field (name "MANUFACTURER") "Generic Components")
        (field (name "PUBLISHER") "Altium Hobart Technology Centre")
      )
      (libsource (lib "RAL") (part "Res-SMD"))
    )
    (comp (ref "R15")
      (value "10R")
      (footprint "RES-SMD-0805")
      (description "Resistor")
      (fields
        (field (name "MANUFACTURER") "Generic Components")
        (field (name "PUBLISHER") "Altium Hobart Technology Centre")
      )
      (libsource (lib "RAL") (part "Res-SMD"))
    )
    (comp (ref "R16")
      (value "51K/1210")
      (footprint "RES-SMD-1210 EX")
      (description "Resistor")
      (fields
        (field (name "MANUFACTURER") "Generic Components")
        (field (name "PUBLISHER") "Altium Hobart Technology Centre")
      )
      (libsource (lib "RAL") (part "Res-SMD"))
    )
    (comp (ref "R17")
      (value "51K/1210")
      (footprint "RES-SMD-1210 EX")
      (description "Resistor")
      (fields
        (field (name "MANUFACTURER") "Generic Components")
        (field (name "PUBLISHER") "Altium Hobart Technology Centre")
      )
      (libsource (lib "RAL") (part "Res-SMD"))
    )
    (comp (ref "R18")
      (value "5.1K")
      (footprint "RES-SMD-0805")
      (description "Resistor")
      (fields
        (field (name "MANUFACTURER") "Generic Components")
        (field (name "PUBLISHER") "Altium Hobart Technology Centre")
      )
      (libsource (lib "RAL") (part "Res-SMD"))
    )
    (comp (ref "R19")
      (value "10R")
      (footprint "RES-SMD-0805")
      (description "Resistor")
      (fields
        (field (name "MANUFACTURER") "Generic Components")
        (field (name "PUBLISHER") "Altium Hobart Technology Centre")
      )
      (libsource (lib "RAL") (part "Res-SMD"))
    )
    (comp (ref "R20")
      (value "2M/1206")
      (footprint "RES-SMD-1206")
      (description "Resistor")
      (fields
        (field (name "MANUFACTURER") "Generic Components")
        (field (name "PUBLISHER") "Altium Hobart Technology Centre")
      )
      (libsource (lib "RAL") (part "Res-SMD"))
    )
    (comp (ref "R21")
      (value "2M/1206")
      (footprint "RES-SMD-1206")
      (description "Resistor")
      (fields
        (field (name "MANUFACTURER") "Generic Components")
        (field (name "PUBLISHER") "Altium Hobart Technology Centre")
      )
      (libsource (lib "RAL") (part "Res-SMD"))
    )
    (comp (ref "R22")
      (value "2M/1206")
      (footprint "RES-SMD-1206")
      (description "Resistor")
      (fields
        (field (name "MANUFACTURER") "Generic Components")
        (field (name "PUBLISHER") "Altium Hobart Technology Centre")
      )
      (libsource (lib "RAL") (part "Res-SMD"))
    )
    (comp (ref "R23")
      (value "2M/1206")
      (footprint "RES-SMD-1206")
      (description "Resistor")
      (fields
        (field (name "MANUFACTURER") "Generic Components")
        (field (name "PUBLISHER") "Altium Hobart Technology Centre")
      )
      (libsource (lib "RAL") (part "Res-SMD"))
    )
    (comp (ref "R24")
      (value "10R")
      (footprint "RES-SMD-0805")
      (description "Resistor")
      (fields
        (field (name "MANUFACTURER") "Generic Components")
        (field (name "PUBLISHER") "Altium Hobart Technology Centre")
      )
      (libsource (lib "RAL") (part "Res-SMD"))
    )
    (comp (ref "R25")
      (value "51K/1210")
      (footprint "RES-SMD-1210 EX")
      (description "Resistor")
      (fields
        (field (name "MANUFACTURER") "Generic Components")
        (field (name "PUBLISHER") "Altium Hobart Technology Centre")
      )
      (libsource (lib "RAL") (part "Res-SMD"))
    )
    (comp (ref "R26")
      (value "51K/1210")
      (footprint "RES-SMD-1210 EX")
      (description "Resistor")
      (fields
        (field (name "MANUFACTURER") "Generic Components")
        (field (name "PUBLISHER") "Altium Hobart Technology Centre")
      )
      (libsource (lib "RAL") (part "Res-SMD"))
    )
    (comp (ref "R27")
      (value "2M/1206")
      (footprint "RES-SMD-1206")
      (description "Resistor")
      (fields
        (field (name "MANUFACTURER") "Generic Components")
        (field (name "PUBLISHER") "Altium Hobart Technology Centre")
      )
      (libsource (lib "RAL") (part "Res-SMD"))
    )
    (comp (ref "R28")
      (value "2M/1206")
      (footprint "RES-SMD-1206")
      (description "Resistor")
      (fields
        (field (name "MANUFACTURER") "Generic Components")
        (field (name "PUBLISHER") "Altium Hobart Technology Centre")
      )
      (libsource (lib "RAL") (part "Res-SMD"))
    )
    (comp (ref "R29")
      (value "2M/1206")
      (footprint "RES-SMD-1206")
      (description "Resistor")
      (fields
        (field (name "MANUFACTURER") "Generic Components")
        (field (name "PUBLISHER") "Altium Hobart Technology Centre")
      )
      (libsource (lib "RAL") (part "Res-SMD"))
    )
    (comp (ref "R30")
      (value "2M/1206")
      (footprint "RES-SMD-1206")
      (description "Resistor")
      (fields
        (field (name "MANUFACTURER") "Generic Components")
        (field (name "PUBLISHER") "Altium Hobart Technology Centre")
      )
      (libsource (lib "RAL") (part "Res-SMD"))
    )
    (comp (ref "R31")
      (value "2M/1206")
      (footprint "RES-SMD-1206")
      (description "Resistor")
      (fields
        (field (name "MANUFACTURER") "Generic Components")
        (field (name "PUBLISHER") "Altium Hobart Technology Centre")
      )
      (libsource (lib "RAL") (part "Res-SMD"))
    )
    (comp (ref "R32")
      (value "2M/1206")
      (footprint "RES-SMD-1206")
      (description "Resistor")
      (fields
        (field (name "MANUFACTURER") "Generic Components")
        (field (name "PUBLISHER") "Altium Hobart Technology Centre")
      )
      (libsource (lib "RAL") (part "Res-SMD"))
    )
    (comp (ref "R33")
      (value "2M/1206")
      (footprint "RES-SMD-1206")
      (description "Resistor")
      (fields
        (field (name "MANUFACTURER") "Generic Components")
        (field (name "PUBLISHER") "Altium Hobart Technology Centre")
      )
      (libsource (lib "RAL") (part "Res-SMD"))
    )
    (comp (ref "R34")
      (value "2M/1206")
      (footprint "RES-SMD-1206")
      (description "Resistor")
      (fields
        (field (name "MANUFACTURER") "Generic Components")
        (field (name "PUBLISHER") "Altium Hobart Technology Centre")
      )
      (libsource (lib "RAL") (part "Res-SMD"))
    )
    (comp (ref "R35")
      (value "5.1K")
      (footprint "RES-SMD-0805")
      (description "Resistor")
      (fields
        (field (name "MANUFACTURER") "Generic Components")
        (field (name "PUBLISHER") "Altium Hobart Technology Centre")
      )
      (libsource (lib "RAL") (part "Res-SMD"))
    )
    (comp (ref "R36")
      (value "10R")
      (footprint "RES-SMD-0805")
      (description "Resistor")
      (fields
        (field (name "MANUFACTURER") "Generic Components")
        (field (name "PUBLISHER") "Altium Hobart Technology Centre")
      )
      (libsource (lib "RAL") (part "Res-SMD"))
    )
    (comp (ref "R37")
      (value "51K/1210")
      (footprint "RES-SMD-1210 EX")
      (description "Resistor")
      (fields
        (field (name "MANUFACTURER") "Generic Components")
        (field (name "PUBLISHER") "Altium Hobart Technology Centre")
      )
      (libsource (lib "RAL") (part "Res-SMD"))
    )
    (comp (ref "R38")
      (value "51K/1210")
      (footprint "RES-SMD-1210 EX")
      (description "Resistor")
      (fields
        (field (name "MANUFACTURER") "Generic Components")
        (field (name "PUBLISHER") "Altium Hobart Technology Centre")
      )
      (libsource (lib "RAL") (part "Res-SMD"))
    )
    (comp (ref "R39")
      (value "10R")
      (footprint "RES-SMD-0805")
      (description "Resistor")
      (fields
        (field (name "MANUFACTURER") "Generic Components")
        (field (name "PUBLISHER") "Altium Hobart Technology Centre")
      )
      (libsource (lib "RAL") (part "Res-SMD"))
    )
    (comp (ref "R40")
      (value "499K")
      (footprint "RES-SMD-1206")
      (description "Resistor")
      (fields
        (field (name "MANUFACTURER") "Generic Components")
        (field (name "PUBLISHER") "Altium Hobart Technology Centre")
      )
      (libsource (lib "RAL") (part "Res-SMD"))
    )
    (comp (ref "R41")
      (value "499K")
      (footprint "RES-SMD-1206")
      (description "Resistor")
      (fields
        (field (name "MANUFACTURER") "Generic Components")
        (field (name "PUBLISHER") "Altium Hobart Technology Centre")
      )
      (libsource (lib "RAL") (part "Res-SMD"))
    )
    (comp (ref "R42")
      (value "499K")
      (footprint "RES-SMD-1206")
      (description "Resistor")
      (fields
        (field (name "MANUFACTURER") "Generic Components")
        (field (name "PUBLISHER") "Altium Hobart Technology Centre")
      )
      (libsource (lib "RAL") (part "Res-SMD"))
    )
    (comp (ref "R43")
      (value "499K")
      (footprint "RES-SMD-1206")
      (description "Resistor")
      (fields
        (field (name "MANUFACTURER") "Generic Components")
        (field (name "PUBLISHER") "Altium Hobart Technology Centre")
      )
      (libsource (lib "RAL") (part "Res-SMD"))
    )
    (comp (ref "R44")
      (value "5.1K")
      (footprint "RES-SMD-0805")
      (description "Resistor")
      (fields
        (field (name "MANUFACTURER") "Generic Components")
        (field (name "PUBLISHER") "Altium Hobart Technology Centre")
      )
      (libsource (lib "RAL") (part "Res-SMD"))
    )
    (comp (ref "R45")
      (value "200K")
      (footprint "RES-SMD-1206")
      (description "Resistor")
      (fields
        (field (name "MANUFACTURER") "Generic Components")
        (field (name "PUBLISHER") "Altium Hobart Technology Centre")
      )
      (libsource (lib "RAL") (part "Res-SMD"))
    )
    (comp (ref "R46")
      (value "499K")
      (footprint "RES-SMD-1206")
      (description "Resistor")
      (fields
        (field (name "MANUFACTURER") "Generic Components")
        (field (name "PUBLISHER") "Altium Hobart Technology Centre")
      )
      (libsource (lib "RAL") (part "Res-SMD"))
    )
    (comp (ref "R47")
      (value "10R")
      (footprint "RES-SMD-0805")
      (description "Resistor")
      (fields
        (field (name "MANUFACTURER") "Generic Components")
        (field (name "PUBLISHER") "Altium Hobart Technology Centre")
      )
      (libsource (lib "RAL") (part "Res-SMD"))
    )
    (comp (ref "R48")
      (value "5.1K")
      (footprint "RES-SMD-0805")
      (description "Resistor")
      (fields
        (field (name "MANUFACTURER") "Generic Components")
        (field (name "PUBLISHER") "Altium Hobart Technology Centre")
      )
      (libsource (lib "RAL") (part "Res-SMD"))
    )
    (comp (ref "R49")
      (value "200K")
      (footprint "RES-SMD-1206")
      (description "Resistor")
      (fields
        (field (name "MANUFACTURER") "Generic Components")
        (field (name "PUBLISHER") "Altium Hobart Technology Centre")
      )
      (libsource (lib "RAL") (part "Res-SMD"))
    )
    (comp (ref "R50")
      (value "499K")
      (footprint "RES-SMD-1206")
      (description "Resistor")
      (fields
        (field (name "MANUFACTURER") "Generic Components")
        (field (name "PUBLISHER") "Altium Hobart Technology Centre")
      )
      (libsource (lib "RAL") (part "Res-SMD"))
    )
    (comp (ref "R51")
      (value "10R")
      (footprint "RES-SMD-0805")
      (description "Resistor")
      (fields
        (field (name "MANUFACTURER") "Generic Components")
        (field (name "PUBLISHER") "Altium Hobart Technology Centre")
      )
      (libsource (lib "RAL") (part "Res-SMD"))
    )
    (comp (ref "R52")
      (value "2M")
      (footprint "RES-SMD-1206")
      (description "Resistor")
      (fields
        (field (name "MANUFACTURER") "Generic Components")
        (field (name "PUBLISHER") "Altium Hobart Technology Centre")
      )
      (libsource (lib "RAL") (part "Res-SMD"))
    )
    (comp (ref "R53")
      (value "5.1K")
      (footprint "RES-SMD-0805")
      (description "Resistor")
      (fields
        (field (name "MANUFACTURER") "Generic Components")
        (field (name "PUBLISHER") "Altium Hobart Technology Centre")
      )
      (libsource (lib "RAL") (part "Res-SMD"))
    )
    (comp (ref "R54")
      (value "200K")
      (footprint "RES-SMD-1206")
      (description "Resistor")
      (fields
        (field (name "MANUFACTURER") "Generic Components")
        (field (name "PUBLISHER") "Altium Hobart Technology Centre")
      )
      (libsource (lib "RAL") (part "Res-SMD"))
    )
    (comp (ref "R55")
      (value "499K")
      (footprint "RES-SMD-1206")
      (description "Resistor")
      (fields
        (field (name "MANUFACTURER") "Generic Components")
        (field (name "PUBLISHER") "Altium Hobart Technology Centre")
      )
      (libsource (lib "RAL") (part "Res-SMD"))
    )
    (comp (ref "R56")
      (value "2M")
      (footprint "RES-SMD-1206")
      (description "Resistor")
      (fields
        (field (name "MANUFACTURER") "Generic Components")
        (field (name "PUBLISHER") "Altium Hobart Technology Centre")
      )
      (libsource (lib "RAL") (part "Res-SMD"))
    )
    (comp (ref "R57")
      (value "200K")
      (footprint "RES-SMD-1206")
      (description "Resistor")
      (fields
        (field (name "MANUFACTURER") "Generic Components")
        (field (name "PUBLISHER") "Altium Hobart Technology Centre")
      )
      (libsource (lib "RAL") (part "Res-SMD"))
    )
    (comp (ref "R58")
      (value "499K")
      (footprint "RES-SMD-1206")
      (description "Resistor")
      (fields
        (field (name "MANUFACTURER") "Generic Components")
        (field (name "PUBLISHER") "Altium Hobart Technology Centre")
      )
      (libsource (lib "RAL") (part "Res-SMD"))
    )
    (comp (ref "R59")
      (value "2M")
      (footprint "RES-SMD-1206")
      (description "Resistor")
      (fields
        (field (name "MANUFACTURER") "Generic Components")
        (field (name "PUBLISHER") "Altium Hobart Technology Centre")
      )
      (libsource (lib "RAL") (part "Res-SMD"))
    )
    (comp (ref "R60")
      (value "200K")
      (footprint "RES-SMD-1206")
      (description "Resistor")
      (fields
        (field (name "MANUFACTURER") "Generic Components")
        (field (name "PUBLISHER") "Altium Hobart Technology Centre")
      )
      (libsource (lib "RAL") (part "Res-SMD"))
    )
    (comp (ref "R61")
      (value "30R/2010")
      (footprint "RES-SMD-1210")
      (description "Resistor")
      (fields
        (field (name "MANUFACTURER") "Generic Components")
        (field (name "PUBLISHER") "Altium Hobart Technology Centre")
      )
      (libsource (lib "RAL") (part "Res-SMD"))
    )
    (comp (ref "R62")
      (value "30R/2010")
      (footprint "RES-SMD-1210")
      (description "Resistor")
      (fields
        (field (name "MANUFACTURER") "Generic Components")
        (field (name "PUBLISHER") "Altium Hobart Technology Centre")
      )
      (libsource (lib "RAL") (part "Res-SMD"))
    )
    (comp (ref "R63")
      (value "0R")
      (footprint "RES-SMD-1206")
      (description "Resistor")
      (fields
        (field (name "MANUFACTURER") "Generic Components")
        (field (name "PUBLISHER") "Altium Hobart Technology Centre")
      )
      (libsource (lib "RAL") (part "Res-SMD"))
    )
    (comp (ref "R64")
      (value "10K")
      (footprint "RES-SMD-0805")
      (description "Resistor")
      (fields
        (field (name "MANUFACTURER") "Generic Components")
        (field (name "PUBLISHER") "Altium Hobart Technology Centre")
      )
      (libsource (lib "RAL") (part "Res-SMD"))
    )
    (comp (ref "R65")
      (value "10K/2010")
      (footprint "RES-SMD-1206")
      (description "Resistor")
      (fields
        (field (name "MANUFACTURER") "Generic Components")
        (field (name "PUBLISHER") "Altium Hobart Technology Centre")
      )
      (libsource (lib "RAL") (part "Res-SMD"))
    )
    (comp (ref "R66")
      (value "2K/1206")
      (footprint "RES-SMD-1206")
      (description "Resistor")
      (fields
        (field (name "MANUFACTURER") "Generic Components")
        (field (name "PUBLISHER") "Altium Hobart Technology Centre")
      )
      (libsource (lib "RAL") (part "Res-SMD"))
    )
    (comp (ref "R67")
      (value "10K/2010")
      (footprint "RES-SMD-0805")
      (description "Resistor")
      (fields
        (field (name "MANUFACTURER") "Generic Components")
        (field (name "PUBLISHER") "Altium Hobart Technology Centre")
      )
      (libsource (lib "RAL") (part "Res-SMD"))
    )
    (comp (ref "R68")
      (value "499K")
      (footprint "RES-SMD-1206")
      (description "Resistor")
      (fields
        (field (name "MANUFACTURER") "Generic Components")
        (field (name "PUBLISHER") "Altium Hobart Technology Centre")
      )
      (libsource (lib "RAL") (part "Res-SMD"))
    )
    (comp (ref "R69")
      (value "10K")
      (footprint "RES-SMD-0805")
      (description "Resistor")
      (fields
        (field (name "MANUFACTURER") "Generic Components")
        (field (name "PUBLISHER") "Altium Hobart Technology Centre")
      )
      (libsource (lib "RAL") (part "Res-SMD"))
    )
    (comp (ref "R70")
      (value "10K/2010")
      (footprint "RES-SMD-1210")
      (description "Resistor")
      (fields
        (field (name "MANUFACTURER") "Generic Components")
        (field (name "PUBLISHER") "Altium Hobart Technology Centre")
      )
      (libsource (lib "RAL") (part "Res-SMD"))
    )
    (comp (ref "R71")
      (value "10K/2010")
      (footprint "RES-SMD-1210")
      (description "Resistor")
      (fields
        (field (name "MANUFACTURER") "Generic Components")
        (field (name "PUBLISHER") "Altium Hobart Technology Centre")
      )
      (libsource (lib "RAL") (part "Res-SMD"))
    )
    (comp (ref "R72")
      (value "10K/2010")
      (footprint "RES-SMD-1210")
      (description "Resistor")
      (fields
        (field (name "MANUFACTURER") "Generic Components")
        (field (name "PUBLISHER") "Altium Hobart Technology Centre")
      )
      (libsource (lib "RAL") (part "Res-SMD"))
    )
    (comp (ref "R73")
      (value "10K/2010")
      (footprint "RES-SMD-1210")
      (description "Resistor")
      (fields
        (field (name "MANUFACTURER") "Generic Components")
        (field (name "PUBLISHER") "Altium Hobart Technology Centre")
      )
      (libsource (lib "RAL") (part "Res-SMD"))
    )
    (comp (ref "R74")
      (value "10K/2010")
      (footprint "RES-SMD-1210")
      (description "Resistor")
      (fields
        (field (name "MANUFACTURER") "Generic Components")
        (field (name "PUBLISHER") "Altium Hobart Technology Centre")
      )
      (libsource (lib "RAL") (part "Res-SMD"))
    )
    (comp (ref "R75")
      (value "10K/2010")
      (footprint "RES-SMD-1210")
      (description "Resistor")
      (fields
        (field (name "MANUFACTURER") "Generic Components")
        (field (name "PUBLISHER") "Altium Hobart Technology Centre")
      )
      (libsource (lib "RAL") (part "Res-SMD"))
    )
    (comp (ref "R76")
      (value "5.1K/1206")
      (footprint "RES-SMD-1206")
      (description "Resistor")
      (fields
        (field (name "MANUFACTURER") "Generic Components")
        (field (name "PUBLISHER") "Altium Hobart Technology Centre")
      )
      (libsource (lib "RAL") (part "Res-SMD"))
    )
    (comp (ref "R77")
      (value "5.1K")
      (footprint "RES-SMD-0805")
      (description "Resistor")
      (fields
        (field (name "MANUFACTURER") "Generic Components")
        (field (name "PUBLISHER") "Altium Hobart Technology Centre")
      )
      (libsource (lib "RAL") (part "Res-SMD"))
    )
    (comp (ref "R78")
      (value "2M")
      (footprint "RES-SMD-1206")
      (description "Resistor")
      (fields
        (field (name "MANUFACTURER") "Generic Components")
        (field (name "PUBLISHER") "Altium Hobart Technology Centre")
      )
      (libsource (lib "RAL") (part "Res-SMD"))
    )
    (comp (ref "R79")
      (value "10K/2010")
      (footprint "RES-SMD-1206")
      (description "Resistor")
      (fields
        (field (name "MANUFACTURER") "Generic Components")
        (field (name "PUBLISHER") "Altium Hobart Technology Centre")
      )
      (libsource (lib "RAL") (part "Res-SMD"))
    )
    (comp (ref "R80")
      (value "10R/0805")
      (footprint "RES-SMD-0805")
      (description "Resistor")
      (fields
        (field (name "MANUFACTURER") "Generic Components")
        (field (name "PUBLISHER") "Altium Hobart Technology Centre")
      )
      (libsource (lib "RAL") (part "Res-SMD"))
    )
    (comp (ref "R81")
      (value "2M")
      (footprint "RES-SMD-1206")
      (description "Resistor")
      (fields
        (field (name "MANUFACTURER") "Generic Components")
        (field (name "PUBLISHER") "Altium Hobart Technology Centre")
      )
      (libsource (lib "RAL") (part "Res-SMD"))
    )
    (comp (ref "R82")
      (value "0R")
      (footprint "RES-SMD-0805")
      (description "Resistor")
      (fields
        (field (name "MANUFACTURER") "Generic Components")
        (field (name "PUBLISHER") "Altium Hobart Technology Centre")
      )
      (libsource (lib "RAL") (part "Res-SMD"))
    )
    (comp (ref "R83")
      (value "30K")
      (footprint "RES-SMD-0805")
      (description "Resistor")
      (fields
        (field (name "MANUFACTURER") "Generic Components")
        (field (name "PUBLISHER") "Altium Hobart Technology Centre")
      )
      (libsource (lib "RAL") (part "Res-SMD"))
    )
    (comp (ref "R84")
      (value "10R")
      (footprint "RES-SMD-1206")
      (description "Resistor")
      (fields
        (field (name "MANUFACTURER") "Generic Components")
        (field (name "PUBLISHER") "Altium Hobart Technology Centre")
      )
      (libsource (lib "RAL") (part "Res-SMD"))
    )
    (comp (ref "R85")
      (value "10K/0805")
      (footprint "RES-SMD-0805")
      (description "Resistor")
      (fields
        (field (name "MANUFACTURER") "Generic Components")
        (field (name "PUBLISHER") "Altium Hobart Technology Centre")
      )
      (libsource (lib "RAL") (part "Res-SMD"))
    )
    (comp (ref "R86")
      (value "2M")
      (footprint "RES-SMD-1206")
      (description "Resistor")
      (fields
        (field (name "MANUFACTURER") "Generic Components")
        (field (name "PUBLISHER") "Altium Hobart Technology Centre")
      )
      (libsource (lib "RAL") (part "Res-SMD"))
    )
    (comp (ref "R87")
      (value "5.1K/0805")
      (footprint "RES-SMD-0805 EX")
      (description "Resistor")
      (fields
        (field (name "MANUFACTURER") "Generic Components")
        (field (name "PUBLISHER") "Altium Hobart Technology Centre")
      )
      (libsource (lib "RAL") (part "Res-SMD"))
    )
    (comp (ref "R88")
      (value "1K")
      (footprint "RES-SMD-1210")
      (description "Resistor")
      (fields
        (field (name "MANUFACTURER") "Generic Components")
        (field (name "PUBLISHER") "Altium Hobart Technology Centre")
      )
      (libsource (lib "RAL") (part "Res-SMD"))
    )
    (comp (ref "R89")
      (value "100R")
      (footprint "RES-SMD-0805")
      (description "Resistor")
      (fields
        (field (name "MANUFACTURER") "Generic Components")
        (field (name "PUBLISHER") "Altium Hobart Technology Centre")
      )
      (libsource (lib "RAL") (part "Res-SMD"))
    )
    (comp (ref "R90")
      (value "150R/1206")
      (footprint "RES-SMD-1206")
      (description "Resistor")
      (fields
        (field (name "MANUFACTURER") "Generic Components")
        (field (name "PUBLISHER") "Altium Hobart Technology Centre")
      )
      (libsource (lib "RAL") (part "Res-SMD"))
    )
    (comp (ref "R91")
      (value "150R/1206")
      (footprint "RES-SMD-1206")
      (description "Resistor")
      (fields
        (field (name "MANUFACTURER") "Generic Components")
        (field (name "PUBLISHER") "Altium Hobart Technology Centre")
      )
      (libsource (lib "RAL") (part "Res-SMD"))
    )
    (comp (ref "R92")
      (value "10R/0805")
      (footprint "RES-SMD-0805")
      (description "Resistor")
      (fields
        (field (name "MANUFACTURER") "Generic Components")
        (field (name "PUBLISHER") "Altium Hobart Technology Centre")
      )
      (libsource (lib "RAL") (part "Res-SMD"))
    )
    (comp (ref "R93")
      (value "0.33R/2010")
      (footprint "RES-SMD-1210")
      (description "Resistor")
      (fields
        (field (name "MANUFACTURER") "Generic Components")
        (field (name "PUBLISHER") "Altium Hobart Technology Centre")
      )
      (libsource (lib "RAL") (part "Res-SMD"))
    )
    (comp (ref "R94")
      (value "0.33R/2010")
      (footprint "RES-SMD-1210")
      (description "Resistor")
      (fields
        (field (name "MANUFACTURER") "Generic Components")
        (field (name "PUBLISHER") "Altium Hobart Technology Centre")
      )
      (libsource (lib "RAL") (part "Res-SMD"))
    )
    (comp (ref "R95")
      (value "0R")
      (footprint "RES-SMD-1206")
      (description "Resistor")
      (fields
        (field (name "MANUFACTURER") "Generic Components")
        (field (name "PUBLISHER") "Altium Hobart Technology Centre")
      )
      (libsource (lib "RAL") (part "Res-SMD"))
    )
    (comp (ref "R96")
      (value "2K/1206")
      (footprint "RES-SMD-1206")
      (description "Resistor")
      (fields
        (field (name "MANUFACTURER") "Generic Components")
        (field (name "PUBLISHER") "Altium Hobart Technology Centre")
      )
      (libsource (lib "RAL") (part "Res-SMD"))
    )
    (comp (ref "R97")
      (value "300K")
      (footprint "RES-SMD-0805")
      (description "Resistor")
      (fields
        (field (name "MANUFACTURER") "Generic Components")
        (field (name "PUBLISHER") "Altium Hobart Technology Centre")
      )
      (libsource (lib "RAL") (part "Res-SMD"))
    )
    (comp (ref "R98")
      (value "20K")
      (footprint "RES-SMD-0805")
      (description "Resistor")
      (fields
        (field (name "MANUFACTURER") "Generic Components")
        (field (name "PUBLISHER") "Altium Hobart Technology Centre")
      )
      (libsource (lib "RAL") (part "Res-SMD"))
    )
    (comp (ref "R99")
      (value "5.1K")
      (footprint "RES-SMD-0805")
      (description "Resistor")
      (fields
        (field (name "MANUFACTURER") "Generic Components")
        (field (name "PUBLISHER") "Altium Hobart Technology Centre")
      )
      (libsource (lib "RAL") (part "Res-SMD"))
    )
    (comp (ref "R100")
      (value "100K")
      (footprint "RES-SMD-0805")
      (description "Resistor")
      (fields
        (field (name "MANUFACTURER") "Generic Components")
        (field (name "PUBLISHER") "Altium Hobart Technology Centre")
      )
      (libsource (lib "RAL") (part "Res-SMD"))
    )
    (comp (ref "R101")
      (value "15K")
      (footprint "RES-SMD-0805")
      (description "Resistor")
      (fields
        (field (name "MANUFACTURER") "Generic Components")
        (field (name "PUBLISHER") "Altium Hobart Technology Centre")
      )
      (libsource (lib "RAL") (part "Res-SMD"))
    )
    (comp (ref "R102")
      (value "5.1K/1206")
      (footprint "RES-SMD-1206")
      (description "Resistor")
      (fields
        (field (name "MANUFACTURER") "Generic Components")
        (field (name "PUBLISHER") "Altium Hobart Technology Centre")
      )
      (libsource (lib "RAL") (part "Res-SMD"))
    )
    (comp (ref "R103")
      (value "30R/1206")
      (footprint "RES-SMD-1206")
      (description "Resistor")
      (fields
        (field (name "MANUFACTURER") "Generic Components")
        (field (name "PUBLISHER") "Altium Hobart Technology Centre")
      )
      (libsource (lib "RAL") (part "Res-SMD"))
    )
    (comp (ref "R104")
      (value "510R")
      (footprint "RES-SMD-0805")
      (description "Resistor")
      (fields
        (field (name "MANUFACTURER") "Generic Components")
        (field (name "PUBLISHER") "Altium Hobart Technology Centre")
      )
      (libsource (lib "RAL") (part "Res-SMD"))
    )
    (comp (ref "R105")
      (value "5.1K")
      (footprint "RES-SMD-0805")
      (description "Resistor")
      (fields
        (field (name "MANUFACTURER") "Generic Components")
        (field (name "PUBLISHER") "Altium Hobart Technology Centre")
      )
      (libsource (lib "RAL") (part "Res-SMD"))
    )
    (comp (ref "R106")
      (value "20k")
      (footprint "RES-SMD-0805")
      (description "Resistor")
      (fields
        (field (name "MANUFACTURER") "Generic Components")
        (field (name "PUBLISHER") "Altium Hobart Technology Centre")
      )
      (libsource (lib "RAL") (part "Res-SMD"))
    )
    (comp (ref "R107")
      (value "100R")
      (footprint "RES-SMD-0805")
      (description "Resistor")
      (fields
        (field (name "MANUFACTURER") "Generic Components")
        (field (name "PUBLISHER") "Altium Hobart Technology Centre")
      )
      (libsource (lib "RAL") (part "Res-SMD"))
    )
    (comp (ref "R108")
      (value "10K/0805")
      (footprint "RES-SMD-0805")
      (description "Resistor")
      (fields
        (field (name "MANUFACTURER") "Generic Components")
        (field (name "PUBLISHER") "Altium Hobart Technology Centre")
      )
      (libsource (lib "RAL") (part "Res-SMD"))
    )
    (comp (ref "R109")
      (value "430R")
      (footprint "RES-SMD-0805")
      (description "Resistor")
      (fields
        (field (name "MANUFACTURER") "Generic Components")
        (field (name "PUBLISHER") "Altium Hobart Technology Centre")
      )
      (libsource (lib "RAL") (part "Res-SMD"))
    )
    (comp (ref "R110")
      (value "510R")
      (footprint "RES-SMD-0805")
      (description "Resistor")
      (fields
        (field (name "MANUFACTURER") "Generic Components")
        (field (name "PUBLISHER") "Altium Hobart Technology Centre")
      )
      (libsource (lib "RAL") (part "Res-SMD"))
    )
    (comp (ref "R111")
      (value "5.1K")
      (footprint "RES-SMD-0805")
      (description "Resistor")
      (fields
        (field (name "MANUFACTURER") "Generic Components")
        (field (name "PUBLISHER") "Altium Hobart Technology Centre")
      )
      (libsource (lib "RAL") (part "Res-SMD"))
    )
    (comp (ref "R112")
      (value "4.3K")
      (footprint "RES-SMD-0805")
      (description "Resistor")
      (fields
        (field (name "MANUFACTURER") "Generic Components")
        (field (name "PUBLISHER") "Altium Hobart Technology Centre")
      )
      (libsource (lib "RAL") (part "Res-SMD"))
    )
    (comp (ref "R113")
      (value "10R/0805")
      (footprint "RES-SMD-0805")
      (description "Resistor")
      (fields
        (field (name "MANUFACTURER") "Generic Components")
        (field (name "PUBLISHER") "Altium Hobart Technology Centre")
      )
      (libsource (lib "RAL") (part "Res-SMD"))
    )
    (comp (ref "R114")
      (value "100R")
      (footprint "RES-SMD-0805")
      (description "Resistor")
      (fields
        (field (name "MANUFACTURER") "Generic Components")
        (field (name "PUBLISHER") "Altium Hobart Technology Centre")
      )
      (libsource (lib "RAL") (part "Res-SMD"))
    )
    (comp (ref "R115")
      (value "1K")
      (footprint "RES-SMD-0805")
      (description "Resistor")
      (fields
        (field (name "MANUFACTURER") "Generic Components")
        (field (name "PUBLISHER") "Altium Hobart Technology Centre")
      )
      (libsource (lib "RAL") (part "Res-SMD"))
    )
    (comp (ref "R116")
      (value "100K")
      (footprint "RES-SMD-0805")
      (description "Resistor")
      (fields
        (field (name "MANUFACTURER") "Generic Components")
        (field (name "PUBLISHER") "Altium Hobart Technology Centre")
      )
      (libsource (lib "RAL") (part "Res-SMD"))
    )
    (comp (ref "R117")
      (value "0.33R/2010")
      (footprint "RES-SMD-1210 EX")
      (description "Resistor")
      (fields
        (field (name "MANUFACTURER") "Generic Components")
        (field (name "PUBLISHER") "Altium Hobart Technology Centre")
      )
      (libsource (lib "RAL") (part "Res-SMD"))
    )
    (comp (ref "R118")
      (value "0.33R/2010")
      (footprint "RES-SMD-1210 EX")
      (description "Resistor")
      (fields
        (field (name "MANUFACTURER") "Generic Components")
        (field (name "PUBLISHER") "Altium Hobart Technology Centre")
      )
      (libsource (lib "RAL") (part "Res-SMD"))
    )
    (comp (ref "R119")
      (value "0.33R/2010")
      (footprint "RES-SMD-1210 EX")
      (description "Resistor")
      (fields
        (field (name "MANUFACTURER") "Generic Components")
        (field (name "PUBLISHER") "Altium Hobart Technology Centre")
      )
      (libsource (lib "RAL") (part "Res-SMD"))
    )
    (comp (ref "R120")
      (value "0.33R/2010")
      (footprint "RES-SMD-1210 EX")
      (description "Resistor")
      (fields
        (field (name "MANUFACTURER") "Generic Components")
        (field (name "PUBLISHER") "Altium Hobart Technology Centre")
      )
      (libsource (lib "RAL") (part "Res-SMD"))
    )
    (comp (ref "R121")
      (value "5.1K")
      (footprint "RES-SMD-0805")
      (description "Resistor")
      (fields
        (field (name "MANUFACTURER") "Generic Components")
        (field (name "PUBLISHER") "Altium Hobart Technology Centre")
      )
      (libsource (lib "RAL") (part "Res-SMD"))
    )
    (comp (ref "R122")
      (value "22R")
      (footprint "RES-SMD-0805")
      (description "Resistor")
      (fields
        (field (name "MANUFACTURER") "Generic Components")
        (field (name "PUBLISHER") "Altium Hobart Technology Centre")
      )
      (libsource (lib "RAL") (part "Res-SMD"))
    )
    (comp (ref "R123")
      (value "1K")
      (footprint "RES-SMD-0805")
      (description "Resistor")
      (fields
        (field (name "MANUFACTURER") "Generic Components")
        (field (name "PUBLISHER") "Altium Hobart Technology Centre")
      )
      (libsource (lib "RAL") (part "Res-SMD"))
    )
    (comp (ref "R124")
      (value "10K/0805")
      (footprint "RES-SMD-0805")
      (description "Resistor")
      (fields
        (field (name "MANUFACTURER") "Generic Components")
        (field (name "PUBLISHER") "Altium Hobart Technology Centre")
      )
      (libsource (lib "RAL") (part "Res-SMD"))
    )
    (comp (ref "R125")
      (value "4.3K")
      (footprint "RES-SMD-0805")
      (description "Resistor")
      (fields
        (field (name "MANUFACTURER") "Generic Components")
        (field (name "PUBLISHER") "Altium Hobart Technology Centre")
      )
      (libsource (lib "RAL") (part "Res-SMD"))
    )
    (comp (ref "R126")
      (value "1.3K")
      (footprint "RES-SMD-0805")
      (description "Resistor")
      (fields
        (field (name "MANUFACTURER") "Generic Components")
        (field (name "PUBLISHER") "Altium Hobart Technology Centre")
      )
      (libsource (lib "RAL") (part "Res-SMD"))
    )
    (comp (ref "R127")
      (value "10K/1206")
      (footprint "RES-SMD-1206")
      (description "Resistor")
      (fields
        (field (name "MANUFACTURER") "Generic Components")
        (field (name "PUBLISHER") "Altium Hobart Technology Centre")
      )
      (libsource (lib "RAL") (part "Res-SMD"))
    )
    (comp (ref "R128")
      (value "30K")
      (footprint "RES-SMD-0805")
      (description "Resistor")
      (fields
        (field (name "MANUFACTURER") "Generic Components")
        (field (name "PUBLISHER") "Altium Hobart Technology Centre")
      )
      (libsource (lib "RAL") (part "Res-SMD"))
    )
    (comp (ref "R129")
      (value "1K")
      (footprint "RES-SMD-0805")
      (description "Resistor")
      (fields
        (field (name "MANUFACTURER") "Generic Components")
        (field (name "PUBLISHER") "Altium Hobart Technology Centre")
      )
      (libsource (lib "RAL") (part "Res-SMD"))
    )
    (comp (ref "R130")
      (value "100K")
      (footprint "RES-SMD-0805")
      (description "Resistor")
      (fields
        (field (name "MANUFACTURER") "Generic Components")
        (field (name "PUBLISHER") "Altium Hobart Technology Centre")
      )
      (libsource (lib "RAL") (part "Res-SMD"))
    )
    (comp (ref "R131")
      (value "100K/1210")
      (footprint "RES-SMD-1210")
      (description "Resistor")
      (fields
        (field (name "MANUFACTURER") "Generic Components")
        (field (name "PUBLISHER") "Altium Hobart Technology Centre")
      )
      (libsource (lib "RAL") (part "Res-SMD"))
    )
    (comp (ref "R132")
      (value "499K/1206")
      (footprint "RES-SMD-1206")
      (description "Resistor")
      (fields
        (field (name "MANUFACTURER") "Generic Components")
        (field (name "PUBLISHER") "Altium Hobart Technology Centre")
      )
      (libsource (lib "RAL") (part "Res-SMD"))
    )
    (comp (ref "R133")
      (value "499K/1206")
      (footprint "RES-SMD-1206")
      (description "Resistor")
      (fields
        (field (name "MANUFACTURER") "Generic Components")
        (field (name "PUBLISHER") "Altium Hobart Technology Centre")
      )
      (libsource (lib "RAL") (part "Res-SMD"))
    )
    (comp (ref "R134")
      (value "499K/1206")
      (footprint "RES-SMD-1206")
      (description "Resistor")
      (fields
        (field (name "MANUFACTURER") "Generic Components")
        (field (name "PUBLISHER") "Altium Hobart Technology Centre")
      )
      (libsource (lib "RAL") (part "Res-SMD"))
    )
    (comp (ref "R135")
      (value "499K/1206")
      (footprint "RES-SMD-1206")
      (description "Resistor")
      (fields
        (field (name "MANUFACTURER") "Generic Components")
        (field (name "PUBLISHER") "Altium Hobart Technology Centre")
      )
      (libsource (lib "RAL") (part "Res-SMD"))
    )
    (comp (ref "R136")
      (value "100K")
      (footprint "RES-SMD-0805")
      (description "Resistor")
      (fields
        (field (name "MANUFACTURER") "Generic Components")
        (field (name "PUBLISHER") "Altium Hobart Technology Centre")
      )
      (libsource (lib "RAL") (part "Res-SMD"))
    )
    (comp (ref "R137")
      (value "100K/1210")
      (footprint "RES-SMD-1210")
      (description "Resistor")
      (fields
        (field (name "MANUFACTURER") "Generic Components")
        (field (name "PUBLISHER") "Altium Hobart Technology Centre")
      )
      (libsource (lib "RAL") (part "Res-SMD"))
    )
    (comp (ref "R138")
      (value "100K/1210")
      (footprint "RES-SMD-1210")
      (description "Resistor")
      (fields
        (field (name "MANUFACTURER") "Generic Components")
        (field (name "PUBLISHER") "Altium Hobart Technology Centre")
      )
      (libsource (lib "RAL") (part "Res-SMD"))
    )
    (comp (ref "R139")
      (value "499K/1206")
      (footprint "RES-SMD-1206")
      (description "Resistor")
      (fields
        (field (name "MANUFACTURER") "Generic Components")
        (field (name "PUBLISHER") "Altium Hobart Technology Centre")
      )
      (libsource (lib "RAL") (part "Res-SMD"))
    )
    (comp (ref "R140")
      (value "499K/1206")
      (footprint "RES-SMD-1206")
      (description "Resistor")
      (fields
        (field (name "MANUFACTURER") "Generic Components")
        (field (name "PUBLISHER") "Altium Hobart Technology Centre")
      )
      (libsource (lib "RAL") (part "Res-SMD"))
    )
    (comp (ref "R141")
      (value "499K/1206")
      (footprint "RES-SMD-1206")
      (description "Resistor")
      (fields
        (field (name "MANUFACTURER") "Generic Components")
        (field (name "PUBLISHER") "Altium Hobart Technology Centre")
      )
      (libsource (lib "RAL") (part "Res-SMD"))
    )
    (comp (ref "R142")
      (value "499K/1206")
      (footprint "RES-SMD-1206")
      (description "Resistor")
      (fields
        (field (name "MANUFACTURER") "Generic Components")
        (field (name "PUBLISHER") "Altium Hobart Technology Centre")
      )
      (libsource (lib "RAL") (part "Res-SMD"))
    )
    (comp (ref "R144")
      (value "100K/1210")
      (footprint "RES-SMD-1210")
      (description "Resistor")
      (fields
        (field (name "MANUFACTURER") "Generic Components")
        (field (name "PUBLISHER") "Altium Hobart Technology Centre")
      )
      (libsource (lib "RAL") (part "Res-SMD"))
    )
    (comp (ref "R145")
      (value "100K")
      (footprint "RES-SMD-0805")
      (description "Resistor")
      (fields
        (field (name "MANUFACTURER") "Generic Components")
        (field (name "PUBLISHER") "Altium Hobart Technology Centre")
      )
      (libsource (lib "RAL") (part "Res-SMD"))
    )
    (comp (ref "R146")
      (value "0R")
      (footprint "RES-SMD-0805")
      (description "Resistor")
      (fields
        (field (name "MANUFACTURER") "Generic Components")
        (field (name "PUBLISHER") "Altium Hobart Technology Centre")
      )
      (libsource (lib "RAL") (part "Res-SMD"))
    )
    (comp (ref "RV1")
      (value "S20K420")
      (footprint "VAR_B72220S0301K101")
      (description "Varistor 420VAC 8000A(8/20us) B72220S0421K101")
      (fields (field (name "MP") "B72220S0301K101") (field (name "MF") "TDK"))
      (libsource (lib "Lib_RD_Cg") (part "Varistor B772"))
    )
    (comp (ref "RV2")
      (value "S20K420")
      (footprint "VAR_B72220S0301K101")
      (description "Varistor 420VAC 8000A(8/20us) B72220S0421K101")
      (fields (field (name "MP") "B72220S0301K101") (field (name "MF") "TDK"))
      (libsource (lib "Lib_RD_Cg") (part "Varistor B772"))
    )
    (comp (ref "RV3")
      (value "S20K420")
      (footprint "VAR_B72220S0301K101")
      (description "Varistor 420VAC 8000A(8/20us) B72220S0421K101")
      (fields (field (name "MP") "B72220S0301K101") (field (name "MF") "TDK"))
      (libsource (lib "Lib_RD_Cg") (part "Varistor B772"))
    )
    (comp (ref "RV4")
      (value "S20K420")
      (footprint "VAR_B72220S0301K101")
      (description "Varistor 420VAC 8000A(8/20us) B72220S0421K101")
      (fields (field (name "MP") "B72220S0301K101") (field (name "MF") "TDK"))
      (libsource (lib "Lib_RD_Cg") (part "Varistor B772"))
    )
    (comp (ref "T1")
      (value "Tranf6")
      (footprint "tranf6")
      (description "Off-Line Transformer WE-UNIT , L=0.9mH")
      (fields
        (field (name "PARTNO") "749118205")
        (field (name "MANUFACTURER") "Würth Elektronik eiSos GmbH")
        (field (name "CREATED BY") "Otto Christin")
      )
      (libsource (lib "Lib_RD_Cg") (part "Tranf6"))
    )
    (comp (ref "U1")
      (value "PVSS STK-PL")
      (footprint "SENSOR-STK-PL")
      (description "Current Sensor sinomags STK-PL 50")
      (fields (field (name "DESIGNED BY") "VanDungEvn"))
      (libsource (lib "") (part "Sensor STK-PL_1"))
    )
    (comp (ref "U2")
      (value "ULN2003A")
      (footprint "SO16")
      (description "Power Switch/Driver 1:1 Darlington 500mA 16-SOP")
      (fields (field (name "MF") "UMW"))
      (libsource (lib "Lib_RD_Cg") (part "ULN2003A"))
    )
    (comp (ref "U3")
      (value "78M05")
      (footprint "TO252")
      (description "UTC 78D05AAL")
      (libsource (lib "Altium_Lib_by_KhueNguyenCreator") (part "78M05 SMD TO252"))
    )
    (comp (ref "U4")
      (value "LF347")
      (footprint "SO14")
      (description "Low Power Quad Operational Amplifier")
      (fields
        (field (name "MANUFACTURER PART NUMBER") "LF347BD")
        (field (name "MANUFACTURER") "Texas Instruments")
      )
      (libsource (lib "TechMT.VN_Lib_Project v2") (part "LF347"))
    )
    (comp (ref "U5")
      (value "MC7912BD2T")
      (footprint "TO263_123")
      (description "IC -12V")
      (fields (field (name "PUBLISHER") "Altium Limited"))
      (libsource (lib "Lib_RD_Cg") (part "7133_1"))
    )
    (comp (ref "U6")
      (value "ICE3AR0680jz")
      (footprint "PG-DIP-7_L9.5-W6.4-P2.54-LS7.6-BL-PE6")
      (description "HIGH PERFORMANCE CURRENT MODE PWM CONTROLLER")
      (fields (field (name "MP") "UC2845BD1"))
      (libsource (lib "Lib_RD_Cg") (part "ICE3AR0680jz"))
    )
    (comp (ref "U7")
      (value "UC2845A")
      (footprint "SOIC127P600X175-8N")
      (fields (field (name "MF") "ON Semiconductor") (field (name "MP") "UC3843BVD1G"))
      (libsource (lib "Lib_RD_Cg") (part "UC3843BVD1G"))
    )
    (comp (ref "U8")
      (value "617A-3")
      (footprint "OPTO TRANSISTOR_SMD-4")
      (description "OPTOISOLATOR 3.75KV TRANS 4-SOP")
      (fields (field (name "MPN") "VOM617A-2T"))
      (libsource (lib "BYTECH_HW_LIB_2019 (1)") (part "VOM617A-2T"))
    )
    (comp (ref "U9")
      (value "TL431BIDR")
      (footprint "SOIC127P600X175-8N")
      (fields (field (name "MF") "ON Semiconductor") (field (name "MP") "TL431BIDR2G"))
      (libsource (lib "Lib_RD_Cg") (part "TL431BIDR2G"))
    )
    (comp (ref "U10")
      (value "Sensor STK-PL")
      (footprint "SENSOR-STK-PL")
      (description "Current Sensor sinomags STK-PL 50")
      (fields (field (name "DESIGNED BY") "VanDungEvn"))
      (libsource (lib "Lib_RD_Cg") (part "Sensor STK-PL"))
    )
    (comp (ref "VR1")
      (value "EPCOS")
      (footprint "Cap EPCOS 21")
      (description "Chống sét lan truyền B88069X4880S102(ví dụ)")
      (fields (field (name "MP") "B72220S0301K101") (field (name "MF") "TDK"))
      (libsource (lib "Lib_RD_Cg") (part "Varistor B772"))
    )
  )
  (nets
    (net (code "1") (name "+5V") (class "Default")
      (node (ref "C2") (pin "1") (pinfunction "1_1") (pintype "passive"))
      (node (ref "C40") (pin "1") (pinfunction "1_1") (pintype "passive"))
      (node (ref "C49") (pin "1") (pinfunction "1_1") (pintype "passive"))
      (node (ref "C65") (pin "2") (pinfunction "2_2") (pintype "passive"))
      (node (ref "C82") (pin "1") (pinfunction "1_1") (pintype "passive"))
      (node (ref "H8") (pin "15") (pinfunction "15_15") (pintype "passive"))
      (node (ref "H8") (pin "16") (pinfunction "16_16") (pintype "passive"))
      (node (ref "R102") (pin "2") (pinfunction "2_2") (pintype "passive"))
      (node (ref "R66") (pin "2") (pinfunction "2_2") (pintype "passive"))
      (node (ref "R76") (pin "2") (pinfunction "2_2") (pintype "passive"))
      (node (ref "R77") (pin "2") (pinfunction "2_2") (pintype "passive"))
      (node (ref "R96") (pin "2") (pinfunction "2_2") (pintype "passive"))
      (node (ref "U1") (pin "4") (pinfunction "Vcc_4") (pintype "passive"))
      (node (ref "U10") (pin "4") (pinfunction "Vcc_4") (pintype "passive"))
      (node (ref "U3") (pin "3") (pinfunction "OUT_3") (pintype "power_in"))
    )
    (net (code "2") (name "+10V") (class "Default")
      (node (ref "C42") (pin "1") (pinfunction "1_1") (pintype "passive"))
      (node (ref "C43") (pin "1") (pinfunction "1_1") (pintype "passive"))
      (node (ref "C44") (pin "1") (pinfunction "1_1") (pintype "passive"))
      (node (ref "C45") (pin "1") (pinfunction "1_1") (pintype "passive"))
      (node (ref "C46") (pin "1") (pinfunction "1_1") (pintype "passive"))
      (node (ref "C47") (pin "1") (pinfunction "1_1") (pintype "passive"))
      (node (ref "C48") (pin "1") (pinfunction "1_1") (pintype "passive"))
      (node (ref "D1") (pin "1") (pinfunction "A_1") (pintype "passive"))
      (node (ref "D14") (pin "3") (pinfunction "K_3") (pintype "passive"))
      (node (ref "D4") (pin "3") (pinfunction "K_3") (pintype "passive"))
      (node (ref "R114") (pin "1") (pinfunction "1_1") (pintype "passive"))
      (node (ref "R123") (pin "1") (pinfunction "1_1") (pintype "passive"))
      (node (ref "R79") (pin "1") (pinfunction "1_1") (pintype "passive"))
      (node (ref "R8") (pin "1") (pinfunction "1_1") (pintype "passive"))
      (node (ref "R98") (pin "1") (pinfunction "1_1") (pintype "passive"))
      (node (ref "U3") (pin "1") (pinfunction "IN_1") (pintype "power_in"))
    )
    (net (code "3") (name "+12V") (class "Default")
      (node (ref "C18") (pin "1") (pinfunction "1_1") (pintype "passive"))
      (node (ref "C41") (pin "1") (pinfunction "1_1") (pintype "passive"))
      (node (ref "C67") (pin "2") (pinfunction "2_2") (pintype "passive"))
      (node (ref "C68") (pin "2") (pinfunction "2_2") (pintype "passive"))
      (node (ref "C69") (pin "1") (pinfunction "1_1") (pintype "passive"))
      (node (ref "C70") (pin "1") (pinfunction "1_1") (pintype "passive"))
      (node (ref "D21") (pin "3") (pinfunction "K_3") (pintype "passive"))
      (node (ref "H1") (pin "2") (pinfunction "2_2") (pintype "passive"))
      (node (ref "H3") (pin "4") (pinfunction "4_4") (pintype "passive"))
      (node (ref "H6") (pin "4") (pinfunction "4_4") (pintype "passive"))
      (node (ref "H8") (pin "17") (pinfunction "17_17") (pintype "passive"))
      (node (ref "L1") (pin "1") (pinfunction "1_1") (pintype "passive"))
      (node (ref "R100") (pin "2") (pinfunction "2_2") (pintype "passive"))
      (node (ref "R91") (pin "1") (pinfunction "1_1") (pintype "passive"))
      (node (ref "U4") (pin "4") (pinfunction "VCC_4") (pintype "power_in"))
    )
    (net (code "4") (name "-12V") (class "Default")
      (node (ref "C56") (pin "2") (pinfunction "2_2") (pintype "passive"))
      (node (ref "C57") (pin "1") (pinfunction "1_1") (pintype "passive"))
      (node (ref "H8") (pin "13") (pinfunction "13_13") (pintype "passive"))
      (node (ref "U4") (pin "11") (pinfunction "VEE_11") (pintype "power_in"))
      (node (ref "U5") (pin "3") (pinfunction "OUT_3") (pintype "power_in"))
    )
    (net (code "5") (name "/CTR_Relay") (class "Default")
      (node (ref "H8") (pin "18") (pinfunction "18_18") (pintype "passive"))
      (node (ref "R6") (pin "1") (pinfunction "1_1") (pintype "passive"))
    )
    (net (code "6") (name "/Ctr_Fan1") (class "Default")
      (node (ref "H8") (pin "22") (pinfunction "22_22") (pintype "passive"))
      (node (ref "R80") (pin "1") (pinfunction "1_1") (pintype "passive"))
      (node (ref "R85") (pin "1") (pinfunction "1_1") (pintype "passive"))
      (node (ref "R92") (pin "1") (pinfunction "1_1") (pintype "passive"))
    )
    (net (code "7") (name "/Ctr_Fan2") (class "Default")
      (node (ref "H8") (pin "24") (pinfunction "24_24") (pintype "passive"))
      (node (ref "R113") (pin "1") (pinfunction "1_1") (pintype "passive"))
      (node (ref "R124") (pin "1") (pinfunction "1_1") (pintype "passive"))
      (node (ref "R92") (pin "2") (pinfunction "2_2") (pintype "passive"))
    )
    (net (code "8") (name "/EVN_L") (class "Default")
      (node (ref "H8") (pin "7") (pinfunction "7_7") (pintype "passive"))
      (node (ref "R9") (pin "2") (pinfunction "2_2") (pintype "passive"))
    )
    (net (code "9") (name "/EVN_N") (class "Default")
      (node (ref "H8") (pin "8") (pinfunction "8_8") (pintype "passive"))
      (node (ref "R31") (pin "2") (pinfunction "2_2") (pintype "passive"))
    )
    (net (code "10") (name "/Fan_Ss") (class "Default")
      (node (ref "D15") (pin "3") (pinfunction "K_3") (pintype "passive"))
      (node (ref "H8") (pin "12") (pinfunction "12_12") (pintype "passive"))
      (node (ref "R87") (pin "2") (pinfunction "2_2") (pintype "passive"))
    )
    (net (code "11") (name "/L_Out") (class "Default")
      (node (ref "H8") (pin "5") (pinfunction "5_5") (pintype "passive"))
      (node (ref "R23") (pin "2") (pinfunction "2_2") (pintype "passive"))
    )
    (net (code "12") (name "/N_Out") (class "Default")
      (node (ref "H8") (pin "6") (pinfunction "6_6") (pintype "passive"))
      (node (ref "R30") (pin "2") (pinfunction "2_2") (pintype "passive"))
    )
    (net (code "13") (name "/PE PV") (class "Default")
      (node (ref "C30") (pin "1") (pinfunction "1_1") (pintype "passive"))
      (node (ref "C31") (pin "1") (pinfunction "1_1") (pintype "passive"))
      (node (ref "C35") (pin "1") (pinfunction "1_1") (pintype "passive"))
      (node (ref "C36") (pin "1") (pinfunction "1_1") (pintype "passive"))
      (node (ref "C86") (pin "2") (pinfunction "2_2") (pintype "passive"))
      (node (ref "C87") (pin "1") (pinfunction "1_1") (pintype "passive"))
      (node (ref "C90") (pin "1") (pinfunction "1_1") (pintype "passive"))
      (node (ref "C91") (pin "2") (pinfunction "2_2") (pintype "passive"))
      (node (ref "M5") (pin "1") (pinfunction "1_1") (pintype "passive"))
    )
    (net (code "14") (name "/PE_Bus+") (class "Default")
      (node (ref "H8") (pin "4") (pinfunction "4_4") (pintype "passive"))
      (node (ref "R52") (pin "2") (pinfunction "2_2") (pintype "passive"))
    )
    (net (code "15") (name "/PV+") (class "Default")
      (node (ref "H8") (pin "10") (pinfunction "10_10") (pintype "passive"))
      (node (ref "R132") (pin "1") (pinfunction "1_1") (pintype "passive"))
    )
    (net (code "16") (name "/PV-") (class "Default")
      (node (ref "H8") (pin "9") (pinfunction "9_9") (pintype "passive"))
      (node (ref "R139") (pin "1") (pinfunction "1_1") (pintype "passive"))
    )
    (net (code "17") (name "/RL-K1") (class "Default")
      (node (ref "K4") (pin "2") (pinfunction "2_2") (pintype "passive"))
      (node (ref "U2") (pin "13") (pinfunction "OUT4_13") (pintype "passive"))
      (node (ref "U2") (pin "14") (pinfunction "OUT3_14") (pintype "passive"))
    )
    (net (code "18") (name "/RL-K2") (class "Default")
      (node (ref "K2") (pin "2") (pinfunction "2_2") (pintype "passive"))
      (node (ref "U2") (pin "15") (pinfunction "OUT2_15") (pintype "passive"))
      (node (ref "U2") (pin "16") (pinfunction "OUT1_16") (pintype "passive"))
    )
    (net (code "19") (name "/RL-K3") (class "Default")
      (node (ref "K5") (pin "3") (pinfunction "3_3") (pintype "passive"))
      (node (ref "U2") (pin "12") (pinfunction "OUT5_12") (pintype "passive"))
    )
    (net (code "20") (name "/RL-K4") (class "Default")
      (node (ref "K1") (pin "3") (pinfunction "3_3") (pintype "passive"))
      (node (ref "U2") (pin "11") (pinfunction "OUT6_11") (pintype "passive"))
    )
    (net (code "21") (name "/Relay_1") (class "Default")
      (node (ref "H8") (pin "28") (pinfunction "28_28") (pintype "passive"))
      (node (ref "R15") (pin "2") (pinfunction "2_2") (pintype "passive"))
      (node (ref "R18") (pin "1") (pinfunction "1_1") (pintype "passive"))
      (node (ref "R19") (pin "2") (pinfunction "2_2") (pintype "passive"))
    )
    (net (code "22") (name "/Relay_2") (class "Default")
      (node (ref "H8") (pin "27") (pinfunction "27_27") (pintype "passive"))
      (node (ref "R24") (pin "2") (pinfunction "2_2") (pintype "passive"))
      (node (ref "R35") (pin "1") (pinfunction "1_1") (pintype "passive"))
      (node (ref "R36") (pin "2") (pinfunction "2_2") (pintype "passive"))
    )
    (net (code "23") (name "/Relay_3") (class "Default")
      (node (ref "H8") (pin "26") (pinfunction "26_26") (pintype "passive"))
      (node (ref "R39") (pin "2") (pinfunction "2_2") (pintype "passive"))
      (node (ref "R44") (pin "1") (pinfunction "1_1") (pintype "passive"))
    )
    (net (code "24") (name "/Relay_4") (class "Default")
      (node (ref "H8") (pin "25") (pinfunction "25_25") (pintype "passive"))
      (node (ref "R47") (pin "2") (pinfunction "2_2") (pintype "passive"))
      (node (ref "R48") (pin "1") (pinfunction "1_1") (pintype "passive"))
    )
    (net (code "25") (name "/Relay_5") (class "Default")
      (node (ref "H8") (pin "23") (pinfunction "23_23") (pintype "passive"))
      (node (ref "R51") (pin "2") (pinfunction "2_2") (pintype "passive"))
      (node (ref "R53") (pin "1") (pinfunction "1_1") (pintype "passive"))
    )
    (net (code "26") (name "/Ss_IPV") (class "Default")
      (node (ref "C76") (pin "1") (pinfunction "1_1") (pintype "passive"))
      (node (ref "H8") (pin "11") (pinfunction "11_11") (pintype "passive"))
      (node (ref "R107") (pin "1") (pinfunction "1_1") (pintype "passive"))
    )
    (net (code "27") (name "/Ss_Vout_EVN") (class "Default")
      (node (ref "H8") (pin "1") (pinfunction "1_1") (pintype "passive"))
      (node (ref "R3") (pin "1") (pinfunction "1_1") (pintype "passive"))
    )
    (net (code "28") (name "/Ss_Vref_ENV") (class "Default")
      (node (ref "H8") (pin "2") (pinfunction "2_2") (pintype "passive"))
      (node (ref "R4") (pin "1") (pinfunction "1_1") (pintype "passive"))
    )
    (net (code "29") (name "BAT +48") (class "Default")
      (node (ref "C21") (pin "1") (pinfunction "1_1") (pintype "passive"))
      (node (ref "C22") (pin "2") (pinfunction "2_2") (pintype "passive"))
      (node (ref "C23") (pin "1") (pinfunction "1_1") (pintype "passive"))
      (node (ref "R127") (pin "2") (pinfunction "2_2") (pintype "passive"))
      (node (ref "R130") (pin "1") (pinfunction "1_1") (pintype "passive"))
      (node (ref "R63") (pin "2") (pinfunction "2_2") (pintype "passive"))
      (node (ref "R64") (pin "1") (pinfunction "1_1") (pintype "passive"))
      (node (ref "R82") (pin "1") (pinfunction "1_1") (pintype "passive"))
      (node (ref "T1") (pin "7") (pinfunction "7_7") (pintype "passive"))
    )
    (net (code "30") (name "BUS +") (class "Default")
      (node (ref "D8") (pin "1") (pinfunction "A_1") (pintype "passive"))
      (node (ref "K3") (pin "8") (pinfunction "8_8") (pintype "passive"))
      (node (ref "P8") (pin "1") (pinfunction "1_1") (pintype "passive"))
      (node (ref "R40") (pin "1") (pinfunction "1_1") (pintype "passive"))
    )
    (net (code "31") (name "BUS +10{slash}12V") (class "Default")
      (node (ref "C3") (pin "1") (pinfunction "1_1") (pintype "passive"))
      (node (ref "C4") (pin "2") (pinfunction "2_2") (pintype "passive"))
      (node (ref "C5") (pin "2") (pinfunction "2_2") (pintype "passive"))
      (node (ref "D1") (pin "2") (pinfunction "K_2") (pintype "passive"))
      (node (ref "D2") (pin "2") (pinfunction "A_2") (pintype "passive"))
      (node (ref "K1") (pin "2") (pinfunction "2_2") (pintype "passive"))
      (node (ref "K2") (pin "3") (pinfunction "3_3") (pintype "passive"))
      (node (ref "K4") (pin "3") (pinfunction "3_3") (pintype "passive"))
      (node (ref "K5") (pin "2") (pinfunction "2_2") (pintype "passive"))
      (node (ref "Q1") (pin "2") (pinfunction "C_2") (pintype "passive"))
      (node (ref "R7") (pin "2") (pinfunction "2_2") (pintype "passive"))
    )
    (net (code "32") (name "GND") (class "Default")
      (node (ref "C4") (pin "1") (pinfunction "1_1") (pintype "passive"))
      (node (ref "C41") (pin "2") (pinfunction "2_2") (pintype "passive"))
      (node (ref "C5") (pin "1") (pinfunction "1_1") (pintype "passive"))
      (node (ref "C6") (pin "1") (pinfunction "1_1") (pintype "passive"))
      (node (ref "C9") (pin "1") (pinfunction "1_1") (pintype "passive"))
      (node (ref "H8") (pin "19") (pinfunction "19_19") (pintype "passive"))
      (node (ref "Q2") (pin "3") (pinfunction "E_3") (pintype "passive"))
      (node (ref "R18") (pin "2") (pinfunction "2_2") (pintype "passive"))
      (node (ref "R35") (pin "2") (pinfunction "2_2") (pintype "passive"))
      (node (ref "R44") (pin "2") (pinfunction "2_2") (pintype "passive"))
      (node (ref "R48") (pin "2") (pinfunction "2_2") (pintype "passive"))
      (node (ref "R53") (pin "2") (pinfunction "2_2") (pintype "passive"))
      (node (ref "U2") (pin "8") (pinfunction "GND_8") (pintype "passive"))
    )
    (net (code "33") (name "GND_BAT") (class "Default")
      (node (ref "C20") (pin "1") (pinfunction "1_1") (pintype "passive"))
      (node (ref "C21") (pin "2") (pinfunction "2_2") (pintype "passive"))
      (node (ref "C22") (pin "1") (pinfunction "1_1") (pintype "passive"))
      (node (ref "C35") (pin "2") (pinfunction "2_2") (pintype "passive"))
      (node (ref "C36") (pin "2") (pinfunction "2_2") (pintype "passive"))
      (node (ref "C39") (pin "2") (pinfunction "2_2") (pintype "passive"))
      (node (ref "C51") (pin "1") (pinfunction "1_1") (pintype "passive"))
      (node (ref "C52") (pin "1") (pinfunction "1_1") (pintype "passive"))
      (node (ref "C53") (pin "1") (pinfunction "1_1") (pintype "passive"))
      (node (ref "C66") (pin "2") (pinfunction "2_2") (pintype "passive"))
      (node (ref "C73") (pin "1") (pinfunction "1_1") (pintype "passive"))
      (node (ref "C77") (pin "1") (pinfunction "1_1") (pintype "passive"))
      (node (ref "C79") (pin "1") (pinfunction "1_1") (pintype "passive"))
      (node (ref "C80") (pin "1") (pinfunction "1_1") (pintype "passive"))
      (node (ref "C92") (pin "1") (pinfunction "1_1") (pintype "passive"))
      (node (ref "C93") (pin "2") (pinfunction "2_2") (pintype "passive"))
      (node (ref "D20") (pin "1") (pinfunction "A_1") (pintype "passive"))
      (node (ref "D22") (pin "3") (pinfunction "A_3") (pintype "passive"))
      (node (ref "H2") (pin "3") (pinfunction "3_3") (pintype "passive"))
      (node (ref "H2") (pin "4") (pinfunction "4_4") (pintype "passive"))
      (node (ref "Q6") (pin "3") (pinfunction "E_3") (pintype "passive"))
      (node (ref "Q7") (pin "3") (pinfunction "E_3") (pintype "passive"))
      (node (ref "R108") (pin "2") (pinfunction "2_2") (pintype "passive"))
      (node (ref "R117") (pin "2") (pinfunction "2_2") (pintype "passive"))
      (node (ref "R118") (pin "2") (pinfunction "2_2") (pintype "passive"))
      (node (ref "R119") (pin "2") (pinfunction "2_2") (pintype "passive"))
      (node (ref "R120") (pin "2") (pinfunction "2_2") (pintype "passive"))
      (node (ref "R125") (pin "2") (pinfunction "2_2") (pintype "passive"))
      (node (ref "R145") (pin "2") (pinfunction "2_2") (pintype "passive"))
      (node (ref "R88") (pin "2") (pinfunction "2_2") (pintype "passive"))
      (node (ref "T1") (pin "1") (pinfunction "1_1") (pintype "passive"))
      (node (ref "U7") (pin "5") (pinfunction "GND_5") (pintype "passive"))
    )
    (net (code "34") (name "GND_FB") (class "Default")
      (node (ref "BT1") (pin "17") (pinfunction "17_17") (pintype "passive"))
      (node (ref "C1") (pin "2") (pinfunction "2_2") (pintype "passive"))
      (node (ref "C18") (pin "2") (pinfunction "2_2") (pintype "passive"))
      (node (ref "C2") (pin "2") (pinfunction "2_2") (pintype "passive"))
      (node (ref "C3") (pin "2") (pinfunction "2_2") (pintype "passive"))
      (node (ref "C38") (pin "1") (pinfunction "1_1") (pintype "passive"))
      (node (ref "C40") (pin "2") (pinfunction "2_2") (pintype "passive"))
      (node (ref "C42") (pin "2") (pinfunction "2_2") (pintype "passive"))
      (node (ref "C43") (pin "2") (pinfunction "2_2") (pintype "passive"))
      (node (ref "C44") (pin "2") (pinfunction "2_2") (pintype "passive"))
      (node (ref "C45") (pin "2") (pinfunction "2_2") (pintype "passive"))
      (node (ref "C46") (pin "2") (pinfunction "2_2") (pintype "passive"))
      (node (ref "C47") (pin "2") (pinfunction "2_2") (pintype "passive"))
      (node (ref "C48") (pin "2") (pinfunction "2_2") (pintype "passive"))
      (node (ref "C49") (pin "2") (pinfunction "2_2") (pintype "passive"))
      (node (ref "C54") (pin "1") (pinfunction "1_1") (pintype "passive"))
      (node (ref "C55") (pin "1") (pinfunction "1_1") (pintype "passive"))
      (node (ref "C56") (pin "1") (pinfunction "1_1") (pintype "passive"))
      (node (ref "C57") (pin "2") (pinfunction "2_2") (pintype "passive"))
      (node (ref "C64") (pin "1") (pinfunction "1_1") (pintype "passive"))
      (node (ref "C65") (pin "1") (pinfunction "1_1") (pintype "passive"))
      (node (ref "C67") (pin "1") (pinfunction "1_1") (pintype "passive"))
      (node (ref "C68") (pin "1") (pinfunction "1_1") (pintype "passive"))
      (node (ref "C69") (pin "2") (pinfunction "2_2") (pintype "passive"))
      (node (ref "C70") (pin "2") (pinfunction "2_2") (pintype "passive"))
      (node (ref "C76") (pin "2") (pinfunction "2_2") (pintype "passive"))
      (node (ref "C78") (pin "2") (pinfunction "2_2") (pintype "passive"))
      (node (ref "C82") (pin "2") (pinfunction "2_2") (pintype "passive"))
      (node (ref "H1") (pin "1") (pinfunction "1_1") (pintype "passive"))
      (node (ref "H3") (pin "2") (pinfunction "2_2") (pintype "passive"))
      (node (ref "H6") (pin "2") (pinfunction "2_2") (pintype "passive"))
      (node (ref "H8") (pin "14") (pinfunction "14_14") (pintype "passive"))
      (node (ref "L7") (pin "1") (pinfunction "1_1") (pintype "passive"))
      (node (ref "LED1") (pin "2") (pinfunction "2_2") (pintype "passive"))
      (node (ref "Q3") (pin "3") (pinfunction "E_3") (pintype "passive"))
      (node (ref "Q5") (pin "3") (pinfunction "E_3") (pintype "passive"))
      (node (ref "R121") (pin "2") (pinfunction "2_2") (pintype "passive"))
      (node (ref "R124") (pin "2") (pinfunction "2_2") (pintype "passive"))
      (node (ref "R128") (pin "1") (pinfunction "1_1") (pintype "passive"))
      (node (ref "R129") (pin "1") (pinfunction "1_1") (pintype "passive"))
      (node (ref "R7") (pin "1") (pinfunction "1_1") (pintype "passive"))
      (node (ref "R85") (pin "2") (pinfunction "2_2") (pintype "passive"))
      (node (ref "R87") (pin "1") (pinfunction "1_1") (pintype "passive"))
      (node (ref "U1") (pin "3") (pinfunction "Gnd_3") (pintype "passive"))
      (node (ref "U10") (pin "3") (pinfunction "Gnd_3") (pintype "passive"))
      (node (ref "U3") (pin "2") (pinfunction "GND_2") (pintype "power_in"))
      (node (ref "U4") (pin "10") (pinfunction "3_IN+_10") (pintype "input"))
      (node (ref "U4") (pin "12") (pinfunction "4_IN+_12") (pintype "input"))
      (node (ref "U4") (pin "3") (pinfunction "1_IN+_3") (pintype "input"))
      (node (ref "U5") (pin "1") (pinfunction "GND_1") (pintype "power_in"))
      (node (ref "U9") (pin "2") (pinfunction "A_2") (pintype "passive"))
      (node (ref "U9") (pin "3") (pinfunction "A_3") (pintype "passive"))
      (node (ref "U9") (pin "6") (pinfunction "A_6") (pintype "passive"))
      (node (ref "U9") (pin "7") (pinfunction "A_7") (pintype "passive"))
    )
    (net (code "35") (name "G_2") (class "Default")
      (node (ref "BT1") (pin "5") (pinfunction "5_5") (pintype "passive"))
      (node (ref "C37") (pin "1") (pinfunction "1_1") (pintype "passive"))
      (node (ref "C59") (pin "2") (pinfunction "2_2") (pintype "passive"))
      (node (ref "C61") (pin "1") (pinfunction "1_1") (pintype "passive"))
      (node (ref "C62") (pin "2") (pinfunction "2_2") (pintype "passive"))
      (node (ref "C63") (pin "2") (pinfunction "2_2") (pintype "passive"))
      (node (ref "C81") (pin "1") (pinfunction "1_1") (pintype "passive"))
      (node (ref "L4") (pin "2") (pinfunction "2_2") (pintype "passive"))
      (node (ref "L6") (pin "2") (pinfunction "2_2") (pintype "passive"))
      (node (ref "R93") (pin "2") (pinfunction "2_2") (pintype "passive"))
      (node (ref "R94") (pin "2") (pinfunction "2_2") (pintype "passive"))
      (node (ref "R97") (pin "1") (pinfunction "1_1") (pintype "passive"))
      (node (ref "U6") (pin "8") (pinfunction "GND_8") (pintype "passive"))
      (node (ref "U8") (pin "3") (pinfunction "3_3") (pintype "passive"))
    )
    (net (code "36") (name "NEG") (class "Default")
      (node (ref "C86") (pin "1") (pinfunction "1_1") (pintype "passive"))
      (node (ref "C89") (pin "1") (pinfunction "1_1") (pintype "passive"))
      (node (ref "L6") (pin "1") (pinfunction "1_1") (pintype "passive"))
      (node (ref "L7") (pin "2") (pinfunction "2_2") (pintype "passive"))
      (node (ref "L8") (pin "2") (pinfunction "2_2") (pintype "passive"))
      (node (ref "P12") (pin "1") (pinfunction "1_1") (pintype "passive"))
      (node (ref "R142") (pin "1") (pinfunction "1_1") (pintype "passive"))
      (node (ref "R58") (pin "2") (pinfunction "2_2") (pintype "passive"))
    )
    (net (code "37") (name "Net-(BT1-Pad9)") (class "Default")
      (node (ref "BT1") (pin "9") (pinfunction "9_9") (pintype "passive"))
      (node (ref "H5") (pin "2") (pinfunction "2_2") (pintype "passive"))
    )
    (net (code "38") (name "Net-(BT1-Pad11)") (class "Default")
      (node (ref "BT1") (pin "11") (pinfunction "11_11") (pintype "passive"))
      (node (ref "H5") (pin "1") (pinfunction "1_1") (pintype "passive"))
    )
    (net (code "39") (name "Net-(BT1-Pad21)") (class "Default")
      (node (ref "BT1") (pin "21") (pinfunction "21_21") (pintype "passive"))
      (node (ref "C25") (pin "2") (pinfunction "2_2") (pintype "passive"))
      (node (ref "C26") (pin "2") (pinfunction "2_2") (pintype "passive"))
      (node (ref "C27") (pin "2") (pinfunction "2_2") (pintype "passive"))
      (node (ref "C28") (pin "2") (pinfunction "2_2") (pintype "passive"))
      (node (ref "H4") (pin "1") (pinfunction "1_1") (pintype "passive"))
      (node (ref "R67") (pin "2") (pinfunction "2_2") (pintype "passive"))
    )
    (net (code "40") (name "Net-(C10-Pad1)") (class "Default")
      (node (ref "C10") (pin "1") (pinfunction "1_1") (pintype "passive"))
      (node (ref "C11") (pin "1") (pinfunction "1_1") (pintype "passive"))
      (node (ref "P1") (pin "1") (pinfunction "1_1") (pintype "passive"))
      (node (ref "R12") (pin "1") (pinfunction "1_1") (pintype "passive"))
      (node (ref "R14") (pin "1") (pinfunction "1_1") (pintype "passive"))
      (node (ref "U1") (pin "5") (pinfunction "Line_5") (pintype "passive"))
      (node (ref "U1") (pin "6") (pinfunction "Line_6") (pintype "passive"))
      (node (ref "U1") (pin "7") (pinfunction "Line_7") (pintype "passive"))
    )
    (net (code "41") (name "Net-(C10-Pad2)") (class "Default")
      (node (ref "C10") (pin "2") (pinfunction "2_2") (pintype "passive"))
      (node (ref "C11") (pin "2") (pinfunction "2_2") (pintype "passive"))
      (node (ref "C16") (pin "1") (pinfunction "1_1") (pintype "passive"))
      (node (ref "C17") (pin "1") (pinfunction "1_1") (pintype "passive"))
      (node (ref "M1") (pin "1") (pinfunction "1_1") (pintype "passive"))
    )
    (net (code "42") (name "Net-(C12-Pad1)") (class "Default")
      (node (ref "C12") (pin "1") (pinfunction "1_1") (pintype "passive"))
      (node (ref "C14") (pin "2") (pinfunction "2_2") (pintype "passive"))
      (node (ref "K4") (pin "1") (pinfunction "1_1") (pintype "passive"))
      (node (ref "L3") (pin "2") (pinfunction "2_2") (pintype "passive"))
      (node (ref "R37") (pin "2") (pinfunction "2_2") (pintype "passive"))
    )
    (net (code "43") (name "Net-(C12-Pad2)") (class "Default")
      (node (ref "C12") (pin "2") (pinfunction "2_2") (pintype "passive"))
      (node (ref "C8") (pin "1") (pinfunction "1_1") (pintype "passive"))
      (node (ref "K2") (pin "4") (pinfunction "4_4") (pintype "passive"))
      (node (ref "L3") (pin "1") (pinfunction "1_1") (pintype "passive"))
      (node (ref "R13") (pin "1") (pinfunction "1_1") (pintype "passive"))
    )
    (net (code "44") (name "Net-(C13-Pad1)") (class "Default")
      (node (ref "C13") (pin "1") (pinfunction "1_1") (pintype "passive"))
      (node (ref "C15") (pin "1") (pinfunction "1_1") (pintype "passive"))
      (node (ref "L3") (pin "3") (pinfunction "3_3") (pintype "passive"))
      (node (ref "P5") (pin "1") (pinfunction "1_1") (pintype "passive"))
      (node (ref "R27") (pin "1") (pinfunction "1_1") (pintype "passive"))
      (node (ref "RV2") (pin "1") (pinfunction "1_1") (pintype "passive"))
      (node (ref "RV3") (pin "1") (pinfunction "1_1") (pintype "passive"))
    )
    (net (code "45") (name "Net-(C13-Pad2)") (class "Default")
      (node (ref "C13") (pin "2") (pinfunction "2_2") (pintype "passive"))
      (node (ref "C7") (pin "1") (pinfunction "1_1") (pintype "passive"))
      (node (ref "L3") (pin "4") (pinfunction "4_4") (pintype "passive"))
      (node (ref "P3") (pin "1") (pinfunction "1_1") (pintype "passive"))
      (node (ref "R20") (pin "1") (pinfunction "1_1") (pintype "passive"))
      (node (ref "RV1") (pin "1") (pinfunction "1_1") (pintype "passive"))
      (node (ref "RV2") (pin "2") (pinfunction "2_2") (pintype "passive"))
    )
    (net (code "46") (name "Net-(C14-Pad1)") (class "Default")
      (node (ref "C14") (pin "1") (pinfunction "1_1") (pintype "passive"))
      (node (ref "C8") (pin "2") (pinfunction "2_2") (pintype "passive"))
      (node (ref "M2") (pin "1") (pinfunction "1_1") (pintype "passive"))
    )
    (net (code "47") (name "Net-(C15-Pad2)") (class "Default")
      (node (ref "C15") (pin "2") (pinfunction "2_2") (pintype "passive"))
      (node (ref "C7") (pin "2") (pinfunction "2_2") (pintype "passive"))
      (node (ref "M3") (pin "1") (pinfunction "1_1") (pintype "passive"))
      (node (ref "VR1") (pin "2") (pinfunction "2_2") (pintype "passive"))
    )
    (net (code "48") (name "Net-(C16-Pad2)") (class "Default")
      (node (ref "C16") (pin "2") (pinfunction "2_2") (pintype "passive"))
      (node (ref "C17") (pin "2") (pinfunction "2_2") (pintype "passive"))
      (node (ref "K5") (pin "4") (pinfunction "4_4") (pintype "passive"))
      (node (ref "P6") (pin "1") (pinfunction "1_1") (pintype "passive"))
      (node (ref "R34") (pin "1") (pinfunction "1_1") (pintype "passive"))
      (node (ref "R38") (pin "2") (pinfunction "2_2") (pintype "passive"))
    )
    (net (code "49") (name "Net-(C19-Pad2)") (class "Default")
      (node (ref "C19") (pin "2") (pinfunction "2_2") (pintype "passive"))
      (node (ref "R61") (pin "1") (pinfunction "1_1") (pintype "passive"))
      (node (ref "R62") (pin "1") (pinfunction "1_1") (pintype "passive"))
    )
    (net (code "50") (name "Net-(C24-Pad2)") (class "Default")
      (node (ref "C24") (pin "2") (pinfunction "2_2") (pintype "passive"))
      (node (ref "R65") (pin "1") (pinfunction "1_1") (pintype "passive"))
    )
    (net (code "51") (name "Net-(C32-Pad2)") (class "Default")
      (node (ref "C32") (pin "2") (pinfunction "2_2") (pintype "passive"))
      (node (ref "C33") (pin "2") (pinfunction "2_2") (pintype "passive"))
      (node (ref "C34") (pin "2") (pinfunction "2_2") (pintype "passive"))
      (node (ref "C39") (pin "1") (pinfunction "1_1") (pintype "passive"))
      (node (ref "L4") (pin "1") (pinfunction "1_1") (pintype "passive"))
      (node (ref "R68") (pin "2") (pinfunction "2_2") (pintype "passive"))
      (node (ref "T1") (pin "11") (pinfunction "11_11") (pintype "passive"))
    )
    (net (code "52") (name "Net-(C50-Pad1)") (class "Default")
      (node (ref "C50") (pin "1") (pinfunction "1_1") (pintype "passive"))
      (node (ref "R79") (pin "2") (pinfunction "2_2") (pintype "passive"))
    )
    (net (code "53") (name "Net-(C58-Pad1)") (class "Default")
      (node (ref "C58") (pin "1") (pinfunction "1_1") (pintype "passive"))
      (node (ref "R90") (pin "2") (pinfunction "2_2") (pintype "passive"))
    )
    (net (code "54") (name "Net-(C60-Pad1)") (class "Default")
      (node (ref "C60") (pin "1") (pinfunction "1_1") (pintype "passive"))
      (node (ref "R91") (pin "2") (pinfunction "2_2") (pintype "passive"))
    )
    (net (code "55") (name "Net-(C72-Pad1)") (class "Default")
      (node (ref "C72") (pin "1") (pinfunction "1_1") (pintype "passive"))
      (node (ref "R106") (pin "2") (pinfunction "2_2") (pintype "passive"))
      (node (ref "R115") (pin "2") (pinfunction "2_2") (pintype "passive"))
      (node (ref "R125") (pin "1") (pinfunction "1_1") (pintype "passive"))
    )
    (net (code "56") (name "Net-(C72-Pad2)") (class "Default")
      (node (ref "C72") (pin "2") (pinfunction "2_2") (pintype "passive"))
      (node (ref "R106") (pin "1") (pinfunction "1_1") (pintype "passive"))
      (node (ref "R146") (pin "2") (pinfunction "2_2") (pintype "passive"))
    )
    (net (code "57") (name "Net-(C75-Pad1)") (class "Default")
      (node (ref "C75") (pin "1") (pinfunction "1_1") (pintype "passive"))
      (node (ref "R115") (pin "1") (pinfunction "1_1") (pintype "passive"))
      (node (ref "R116") (pin "2") (pinfunction "2_2") (pintype "passive"))
    )
    (net (code "58") (name "Net-(C83-Pad2)") (class "Default")
      (node (ref "C83") (pin "2") (pinfunction "2_2") (pintype "passive"))
      (node (ref "C85") (pin "1") (pinfunction "1_1") (pintype "passive"))
      (node (ref "R126") (pin "2") (pinfunction "2_2") (pintype "passive"))
    )
    (net (code "59") (name "Net-(C87-Pad2)") (class "Default")
      (node (ref "C87") (pin "2") (pinfunction "2_2") (pintype "passive"))
      (node (ref "C88") (pin "2") (pinfunction "2_2") (pintype "passive"))
      (node (ref "L8") (pin "4") (pinfunction "4_4") (pintype "passive"))
      (node (ref "P9") (pin "1") (pinfunction "1_1") (pintype "passive"))
      (node (ref "R131") (pin "1") (pinfunction "1_1") (pintype "passive"))
      (node (ref "RV4") (pin "2") (pinfunction "2_2") (pintype "passive"))
    )
    (net (code "60") (name "Net-(C88-Pad1)") (class "Default")
      (node (ref "C88") (pin "1") (pinfunction "1_1") (pintype "passive"))
      (node (ref "C90") (pin "2") (pinfunction "2_2") (pintype "passive"))
      (node (ref "L8") (pin "3") (pinfunction "3_3") (pintype "passive"))
      (node (ref "P11") (pin "1") (pinfunction "1_1") (pintype "passive"))
      (node (ref "R144") (pin "1") (pinfunction "1_1") (pintype "passive"))
      (node (ref "RV4") (pin "1") (pinfunction "1_1") (pintype "passive"))
    )
    (net (code "61") (name "Net-(C89-Pad2)") (class "Default")
      (node (ref "C89") (pin "2") (pinfunction "2_2") (pintype "passive"))
      (node (ref "C91") (pin "1") (pinfunction "1_1") (pintype "passive"))
      (node (ref "L8") (pin "1") (pinfunction "1_1") (pintype "passive"))
      (node (ref "U10") (pin "10") (pinfunction "Line_10") (pintype "passive"))
      (node (ref "U10") (pin "8") (pinfunction "Line_8") (pintype "passive"))
      (node (ref "U10") (pin "9") (pinfunction "Line_9") (pintype "passive"))
    )
    (net (code "62") (name "Net-(D2-K)") (class "Default")
      (node (ref "D2") (pin "1") (pinfunction "K_1") (pintype "passive"))
      (node (ref "D5") (pin "2") (pinfunction "A_2") (pintype "passive"))
    )
    (net (code "63") (name "Net-(D3-A1)") (class "Default")
      (node (ref "D3") (pin "1") (pinfunction "A1_1") (pintype "passive"))
      (node (ref "D3") (pin "2") (pinfunction "A2_2") (pintype "passive"))
      (node (ref "D4") (pin "1") (pinfunction "A1_1") (pintype "passive"))
      (node (ref "D4") (pin "2") (pinfunction "A2_2") (pintype "passive"))
      (node (ref "K3") (pin "1") (pinfunction "1_1") (pintype "passive"))
    )
    (net (code "64") (name "Net-(D3-K)") (class "Default")
      (node (ref "D3") (pin "3") (pinfunction "K_3") (pintype "passive"))
      (node (ref "U2") (pin "10") (pinfunction "OUT7_10") (pintype "passive"))
    )
    (net (code "65") (name "Net-(D5-K)") (class "Default")
      (node (ref "C6") (pin "2") (pinfunction "2_2") (pintype "passive"))
      (node (ref "C9") (pin "2") (pinfunction "2_2") (pintype "passive"))
      (node (ref "D5") (pin "1") (pinfunction "K_1") (pintype "passive"))
      (node (ref "U2") (pin "9") (pinfunction "COM_9") (pintype "passive"))
    )
    (net (code "66") (name "Net-(D6-A)") (class "Default")
      (node (ref "BT1") (pin "23") (pinfunction "23_23") (pintype "passive"))
      (node (ref "C24") (pin "1") (pinfunction "1_1") (pintype "passive"))
      (node (ref "D6") (pin "1") (pinfunction "A_1") (pintype "passive"))
      (node (ref "D6") (pin "2") (pinfunction "NC_2") (pintype "passive"))
    )
    (net (code "67") (name "Net-(D6-K)") (class "Default")
      (node (ref "C25") (pin "1") (pinfunction "1_1") (pintype "passive"))
      (node (ref "C26") (pin "1") (pinfunction "1_1") (pintype "passive"))
      (node (ref "C27") (pin "1") (pinfunction "1_1") (pintype "passive"))
      (node (ref "C28") (pin "1") (pinfunction "1_1") (pintype "passive"))
      (node (ref "D6") (pin "3") (pinfunction "K_3") (pintype "passive"))
      (node (ref "H4") (pin "2") (pinfunction "2_2") (pintype "passive"))
      (node (ref "R65") (pin "2") (pinfunction "2_2") (pintype "passive"))
      (node (ref "R67") (pin "1") (pinfunction "1_1") (pintype "passive"))
    )
    (net (code "68") (name "Net-(D7-A)") (class "Default")
      (node (ref "C20") (pin "2") (pinfunction "2_2") (pintype "passive"))
      (node (ref "C30") (pin "2") (pinfunction "2_2") (pintype "passive"))
      (node (ref "C31") (pin "2") (pinfunction "2_2") (pintype "passive"))
      (node (ref "D7") (pin "1") (pinfunction "A_1") (pintype "passive"))
      (node (ref "H2") (pin "1") (pinfunction "1_1") (pintype "passive"))
      (node (ref "H2") (pin "2") (pinfunction "2_2") (pintype "passive"))
    )
    (net (code "69") (name "Net-(D7-K)") (class "Default")
      (node (ref "D7") (pin "2") (pinfunction "K_2") (pintype "passive"))
      (node (ref "R63") (pin "1") (pinfunction "1_1") (pintype "passive"))
    )
    (net (code "70") (name "Net-(D10-A)") (class "Default")
      (node (ref "C32") (pin "1") (pinfunction "1_1") (pintype "passive"))
      (node (ref "C33") (pin "1") (pinfunction "1_1") (pintype "passive"))
      (node (ref "C34") (pin "1") (pinfunction "1_1") (pintype "passive"))
      (node (ref "D10") (pin "1") (pinfunction "A_1") (pintype "passive"))
      (node (ref "D11") (pin "1") (pinfunction "K_1") (pintype "passive"))
      (node (ref "R61") (pin "2") (pinfunction "2_2") (pintype "passive"))
      (node (ref "R62") (pin "2") (pinfunction "2_2") (pintype "passive"))
      (node (ref "R68") (pin "1") (pinfunction "1_1") (pintype "passive"))
    )
    (net (code "71") (name "Net-(D10-K)") (class "Default")
      (node (ref "BT1") (pin "1") (pinfunction "1_1") (pintype "passive"))
      (node (ref "C29") (pin "2") (pinfunction "2_2") (pintype "passive"))
      (node (ref "C37") (pin "2") (pinfunction "2_2") (pintype "passive"))
      (node (ref "D10") (pin "2") (pinfunction "K_2") (pintype "passive"))
      (node (ref "D8") (pin "2") (pinfunction "K_2") (pintype "passive"))
      (node (ref "D9") (pin "2") (pinfunction "K_2") (pintype "passive"))
      (node (ref "R70") (pin "2") (pinfunction "2_2") (pintype "passive"))
      (node (ref "R78") (pin "2") (pinfunction "2_2") (pintype "passive"))
    )
    (net (code "72") (name "Net-(D11-A)") (class "Default")
      (node (ref "C19") (pin "1") (pinfunction "1_1") (pintype "passive"))
      (node (ref "D11") (pin "2") (pinfunction "A_2") (pintype "passive"))
      (node (ref "T1") (pin "9") (pinfunction "9_9") (pintype "passive"))
    )
    (net (code "73") (name "Net-(D12-A)") (class "Default")
      (node (ref "D12") (pin "1") (pinfunction "A_1") (pintype "passive"))
      (node (ref "Q4") (pin "2") (pinfunction "D_2") (pintype "passive"))
      (node (ref "T1") (pin "5") (pinfunction "5_5") (pintype "passive"))
    )
    (net (code "74") (name "Net-(D12-K)") (class "Default")
      (node (ref "C23") (pin "2") (pinfunction "2_2") (pintype "passive"))
      (node (ref "D12") (pin "2") (pinfunction "K_2") (pintype "passive"))
      (node (ref "R69") (pin "1") (pinfunction "1_1") (pintype "passive"))
    )
    (net (code "75") (name "Net-(D13-A)") (class "Default")
      (node (ref "BT1") (pin "3") (pinfunction "3_3") (pintype "passive"))
      (node (ref "D13") (pin "1") (pinfunction "A_1") (pintype "passive"))
      (node (ref "U6") (pin "5") (pinfunction "DRAIN_5") (pintype "passive"))
    )
    (net (code "76") (name "Net-(D13-K)") (class "Default")
      (node (ref "C29") (pin "1") (pinfunction "1_1") (pintype "passive"))
      (node (ref "D13") (pin "2") (pinfunction "K_2") (pintype "passive"))
      (node (ref "R75") (pin "1") (pinfunction "1_1") (pintype "passive"))
    )
    (net (code "77") (name "Net-(D14-A)") (class "Default")
      (node (ref "BT1") (pin "19") (pinfunction "19_19") (pintype "passive"))
      (node (ref "C50") (pin "2") (pinfunction "2_2") (pintype "passive"))
      (node (ref "D14") (pin "1") (pinfunction "A_1") (pintype "passive"))
      (node (ref "D14") (pin "2") (pinfunction "NC_2") (pintype "passive"))
    )
    (net (code "78") (name "Net-(D15-A1)") (class "Default")
      (node (ref "C64") (pin "2") (pinfunction "2_2") (pintype "passive"))
      (node (ref "D15") (pin "1") (pinfunction "A1_1") (pintype "passive"))
      (node (ref "H6") (pin "3") (pinfunction "3_3") (pintype "passive"))
      (node (ref "R96") (pin "1") (pinfunction "1_1") (pintype "passive"))
    )
    (net (code "79") (name "Net-(D15-A2)") (class "Default")
      (node (ref "C38") (pin "2") (pinfunction "2_2") (pintype "passive"))
      (node (ref "D15") (pin "2") (pinfunction "A2_2") (pintype "passive"))
      (node (ref "H3") (pin "3") (pinfunction "3_3") (pintype "passive"))
      (node (ref "R66") (pin "1") (pinfunction "1_1") (pintype "passive"))
    )
    (net (code "80") (name "Net-(D16-A1)") (class "Default")
      (node (ref "C52") (pin "2") (pinfunction "2_2") (pintype "passive"))
      (node (ref "C53") (pin "2") (pinfunction "2_2") (pintype "passive"))
      (node (ref "D16") (pin "1") (pinfunction "A1_1") (pintype "passive"))
      (node (ref "D16") (pin "2") (pinfunction "A2_2") (pintype "passive"))
      (node (ref "D17") (pin "2") (pinfunction "K_2") (pintype "passive"))
      (node (ref "R146") (pin "1") (pinfunction "1_1") (pintype "passive"))
      (node (ref "R88") (pin "1") (pinfunction "1_1") (pintype "passive"))
    )
    (net (code "81") (name "Net-(D16-K)") (class "Default")
      (node (ref "D16") (pin "3") (pinfunction "K_3") (pintype "passive"))
      (node (ref "R84") (pin "2") (pinfunction "2_2") (pintype "passive"))
    )
    (net (code "82") (name "Net-(D17-A)") (class "Default")
      (node (ref "D17") (pin "1") (pinfunction "A_1") (pintype "passive"))
      (node (ref "T1") (pin "3") (pinfunction "3_3") (pintype "passive"))
    )
    (net (code "83") (name "Net-(D18-A)") (class "Default")
      (node (ref "BT1") (pin "7") (pinfunction "7_7") (pintype "passive"))
      (node (ref "D18") (pin "1") (pinfunction "A_1") (pintype "passive"))
    )
    (net (code "84") (name "Net-(D18-K)") (class "Default")
      (node (ref "D18") (pin "2") (pinfunction "K_2") (pintype "passive"))
      (node (ref "R89") (pin "1") (pinfunction "1_1") (pintype "passive"))
    )
    (net (code "85") (name "Net-(D19-A)") (class "Default")
      (node (ref "C54") (pin "2") (pinfunction "2_2") (pintype "passive"))
      (node (ref "C55") (pin "2") (pinfunction "2_2") (pintype "passive"))
      (node (ref "D19") (pin "1") (pinfunction "A_1") (pintype "passive"))
      (node (ref "R90") (pin "1") (pinfunction "1_1") (pintype "passive"))
      (node (ref "U5") (pin "2") (pinfunction "IN_2") (pintype "power_in"))
    )
    (net (code "86") (name "Net-(D19-K)") (class "Default")
      (node (ref "BT1") (pin "15") (pinfunction "15_15") (pintype "passive"))
      (node (ref "C58") (pin "2") (pinfunction "2_2") (pintype "passive"))
      (node (ref "D19") (pin "2") (pinfunction "K_2") (pintype "passive"))
    )
    (net (code "87") (name "Net-(D20-K)") (class "Default")
      (node (ref "C51") (pin "2") (pinfunction "2_2") (pintype "passive"))
      (node (ref "D20") (pin "3") (pinfunction "K_3") (pintype "passive"))
      (node (ref "H7") (pin "2") (pinfunction "2_2") (pintype "passive"))
      (node (ref "R83") (pin "2") (pinfunction "2_2") (pintype "passive"))
      (node (ref "R84") (pin "1") (pinfunction "1_1") (pintype "passive"))
      (node (ref "R95") (pin "1") (pinfunction "1_1") (pintype "passive"))
    )
    (net (code "88") (name "Net-(D21-A)") (class "Default")
      (node (ref "BT1") (pin "13") (pinfunction "13_13") (pintype "passive"))
      (node (ref "C60") (pin "2") (pinfunction "2_2") (pintype "passive"))
      (node (ref "D21") (pin "1") (pinfunction "A_1") (pintype "passive"))
      (node (ref "D21") (pin "2") (pinfunction "NC_2") (pintype "passive"))
    )
    (net (code "89") (name "Net-(D23-A)") (class "Default")
      (node (ref "D23") (pin "1") (pinfunction "A_1") (pintype "passive"))
      (node (ref "D24") (pin "3") (pinfunction "K_3") (pintype "passive"))
    )
    (net (code "90") (name "Net-(D23-K)") (class "Default")
      (node (ref "D23") (pin "3") (pinfunction "K_3") (pintype "passive"))
      (node (ref "R127") (pin "1") (pinfunction "1_1") (pintype "passive"))
    )
    (net (code "91") (name "Net-(D24-A)") (class "Default")
      (node (ref "C93") (pin "1") (pinfunction "1_1") (pintype "passive"))
      (node (ref "D24") (pin "1") (pinfunction "A_1") (pintype "passive"))
      (node (ref "Q7") (pin "1") (pinfunction "B_1") (pintype "passive"))
      (node (ref "R145") (pin "1") (pinfunction "1_1") (pintype "passive"))
    )
    (net (code "92") (name "Net-(D25-A)") (class "Default")
      (node (ref "C92") (pin "2") (pinfunction "2_2") (pintype "passive"))
      (node (ref "D25") (pin "3") (pinfunction "A_3") (pintype "passive"))
      (node (ref "R136") (pin "2") (pinfunction "2_2") (pintype "passive"))
    )
    (net (code "93") (name "Net-(K1-Pad1)") (class "Default")
      (node (ref "K1") (pin "1") (pinfunction "1_1") (pintype "passive"))
      (node (ref "K2") (pin "1") (pinfunction "1_1") (pintype "passive"))
      (node (ref "L2") (pin "4") (pinfunction "4_4") (pintype "passive"))
    )
    (net (code "94") (name "Net-(K1-Pad4)") (class "Default")
      (node (ref "K1") (pin "4") (pinfunction "4_4") (pintype "passive"))
      (node (ref "U1") (pin "10") (pinfunction "Line_10") (pintype "passive"))
      (node (ref "U1") (pin "8") (pinfunction "Line_8") (pintype "passive"))
      (node (ref "U1") (pin "9") (pinfunction "Line_9") (pintype "passive"))
    )
    (net (code "95") (name "Net-(K3-Pad4)") (class "Default")
      (node (ref "K3") (pin "4") (pinfunction "4_4") (pintype "passive"))
      (node (ref "K3") (pin "9") (pinfunction "9_9") (pintype "passive"))
    )
    (net (code "96") (name "Net-(K3-Pad5)") (class "Default")
      (node (ref "K3") (pin "5") (pinfunction "5_5") (pintype "passive"))
      (node (ref "R43") (pin "2") (pinfunction "2_2") (pintype "passive"))
      (node (ref "R45") (pin "1") (pinfunction "1_1") (pintype "passive"))
      (node (ref "R46") (pin "1") (pinfunction "1_1") (pintype "passive"))
    )
    (net (code "97") (name "Net-(K3-Pad12)") (class "Default")
      (node (ref "K3") (pin "12") (pinfunction "12_12") (pintype "passive"))
      (node (ref "R8") (pin "2") (pinfunction "2_2") (pintype "passive"))
    )
    (net (code "98") (name "Net-(K4-Pad4)") (class "Default")
      (node (ref "K4") (pin "4") (pinfunction "4_4") (pintype "passive"))
      (node (ref "K5") (pin "1") (pinfunction "1_1") (pintype "passive"))
      (node (ref "L2") (pin "3") (pinfunction "3_3") (pintype "passive"))
    )
    (net (code "99") (name "Net-(L2-Pad1)") (class "Default")
      (node (ref "L2") (pin "1") (pinfunction "1_1") (pintype "passive"))
      (node (ref "P2") (pin "1") (pinfunction "1_1") (pintype "passive"))
    )
    (net (code "100") (name "Net-(L2-Pad2)") (class "Default")
      (node (ref "L2") (pin "2") (pinfunction "2_2") (pintype "passive"))
      (node (ref "P4") (pin "1") (pinfunction "1_1") (pintype "passive"))
    )
    (net (code "101") (name "Net-(LED1-Pad1)") (class "Default")
      (node (ref "LED1") (pin "1") (pinfunction "1_1") (pintype "passive"))
      (node (ref "R77") (pin "1") (pinfunction "1_1") (pintype "passive"))
    )
    (net (code "102") (name "Net-(M4-Pad1)") (class "Default")
      (node (ref "M4") (pin "1") (pinfunction "1_1") (pintype "passive"))
      (node (ref "R59") (pin "1") (pinfunction "1_1") (pintype "passive"))
      (node (ref "R60") (pin "2") (pinfunction "2_2") (pintype "passive"))
    )
    (net (code "103") (name "Net-(P10-Pad1)") (class "Default")
      (node (ref "P10") (pin "1") (pinfunction "1_1") (pintype "passive"))
      (node (ref "R135") (pin "1") (pinfunction "1_1") (pintype "passive"))
      (node (ref "U10") (pin "5") (pinfunction "Line_5") (pintype "passive"))
      (node (ref "U10") (pin "6") (pinfunction "Line_6") (pintype "passive"))
      (node (ref "U10") (pin "7") (pinfunction "Line_7") (pintype "passive"))
    )
    (net (code "104") (name "Net-(Q1-B)") (class "Default")
      (node (ref "Q1") (pin "1") (pinfunction "B_1") (pintype "passive"))
      (node (ref "R2") (pin "1") (pinfunction "1_1") (pintype "passive"))
      (node (ref "R5") (pin "2") (pinfunction "2_2") (pintype "passive"))
    )
    (net (code "105") (name "Net-(Q1-E)") (class "Default")
      (node (ref "C1") (pin "1") (pinfunction "1_1") (pintype "passive"))
      (node (ref "L1") (pin "2") (pinfunction "2_2") (pintype "passive"))
      (node (ref "Q1") (pin "3") (pinfunction "E_3") (pintype "passive"))
      (node (ref "R1") (pin "2") (pinfunction "2_2") (pintype "passive"))
    )
    (net (code "106") (name "Net-(Q2-B)") (class "Default")
      (node (ref "Q2") (pin "1") (pinfunction "B_1") (pintype "passive"))
      (node (ref "R6") (pin "2") (pinfunction "2_2") (pintype "passive"))
    )
    (net (code "107") (name "Net-(Q2-C)") (class "Default")
      (node (ref "Q2") (pin "2") (pinfunction "C_2") (pintype "passive"))
      (node (ref "R1") (pin "1") (pinfunction "1_1") (pintype "passive"))
      (node (ref "R2") (pin "2") (pinfunction "2_2") (pintype "passive"))
      (node (ref "R5") (pin "1") (pinfunction "1_1") (pintype "passive"))
    )
    (net (code "108") (name "Net-(Q3-B)") (class "Default")
      (node (ref "Q3") (pin "1") (pinfunction "B_1") (pintype "passive"))
      (node (ref "R80") (pin "2") (pinfunction "2_2") (pintype "passive"))
    )
    (net (code "109") (name "Net-(Q3-C)") (class "Default")
      (node (ref "H3") (pin "1") (pinfunction "1_1") (pintype "passive"))
      (node (ref "Q3") (pin "2") (pinfunction "C_2") (pintype "passive"))
      (node (ref "R76") (pin "1") (pinfunction "1_1") (pintype "passive"))
    )
    (net (code "110") (name "Net-(Q4-G)") (class "Default")
      (node (ref "Q4") (pin "1") (pinfunction "G_1") (pintype "passive"))
      (node (ref "R103") (pin "1") (pinfunction "1_1") (pintype "passive"))
      (node (ref "R108") (pin "1") (pinfunction "1_1") (pintype "passive"))
    )
    (net (code "111") (name "Net-(Q4-S)") (class "Default")
      (node (ref "Q4") (pin "3") (pinfunction "S_3") (pintype "passive"))
      (node (ref "R109") (pin "1") (pinfunction "1_1") (pintype "passive"))
      (node (ref "R117") (pin "1") (pinfunction "1_1") (pintype "passive"))
      (node (ref "R118") (pin "1") (pinfunction "1_1") (pintype "passive"))
      (node (ref "R119") (pin "1") (pinfunction "1_1") (pintype "passive"))
      (node (ref "R120") (pin "1") (pinfunction "1_1") (pintype "passive"))
    )
    (net (code "112") (name "Net-(Q5-B)") (class "Default")
      (node (ref "Q5") (pin "1") (pinfunction "B_1") (pintype "passive"))
      (node (ref "R113") (pin "2") (pinfunction "2_2") (pintype "passive"))
    )
    (net (code "113") (name "Net-(Q5-C)") (class "Default")
      (node (ref "H6") (pin "1") (pinfunction "1_1") (pintype "passive"))
      (node (ref "Q5") (pin "2") (pinfunction "C_2") (pintype "passive"))
      (node (ref "R102") (pin "1") (pinfunction "1_1") (pintype "passive"))
    )
    (net (code "114") (name "Net-(Q6-B)") (class "Default")
      (node (ref "Q6") (pin "1") (pinfunction "B_1") (pintype "passive"))
      (node (ref "Q7") (pin "2") (pinfunction "C_2") (pintype "passive"))
      (node (ref "R130") (pin "2") (pinfunction "2_2") (pintype "passive"))
    )
    (net (code "115") (name "Net-(Q6-C)") (class "Default")
      (node (ref "C74") (pin "1") (pinfunction "1_1") (pintype "passive"))
      (node (ref "C75") (pin "2") (pinfunction "2_2") (pintype "passive"))
      (node (ref "D25") (pin "1") (pinfunction "C_1") (pintype "passive"))
      (node (ref "Q6") (pin "2") (pinfunction "C_2") (pintype "passive"))
      (node (ref "U7") (pin "1") (pinfunction "COMP_1") (pintype "input"))
    )
    (net (code "116") (name "Net-(R10-Pad1)") (class "Default")
      (node (ref "R10") (pin "1") (pinfunction "1_1") (pintype "passive"))
      (node (ref "R11") (pin "2") (pinfunction "2_2") (pintype "passive"))
    )
    (net (code "117") (name "Net-(R10-Pad2)") (class "Default")
      (node (ref "R10") (pin "2") (pinfunction "2_2") (pintype "passive"))
      (node (ref "R9") (pin "1") (pinfunction "1_1") (pintype "passive"))
    )
    (net (code "118") (name "Net-(R11-Pad1)") (class "Default")
      (node (ref "R11") (pin "1") (pinfunction "1_1") (pintype "passive"))
      (node (ref "R12") (pin "2") (pinfunction "2_2") (pintype "passive"))
    )
    (net (code "119") (name "Net-(R13-Pad2)") (class "Default")
      (node (ref "R13") (pin "2") (pinfunction "2_2") (pintype "passive"))
      (node (ref "R16") (pin "1") (pinfunction "1_1") (pintype "passive"))
    )
    (net (code "120") (name "Net-(R14-Pad2)") (class "Default")
      (node (ref "R14") (pin "2") (pinfunction "2_2") (pintype "passive"))
      (node (ref "R17") (pin "1") (pinfunction "1_1") (pintype "passive"))
    )
    (net (code "121") (name "Net-(R16-Pad2)") (class "Default")
      (node (ref "R16") (pin "2") (pinfunction "2_2") (pintype "passive"))
      (node (ref "R25") (pin "1") (pinfunction "1_1") (pintype "passive"))
    )
    (net (code "122") (name "Net-(R17-Pad2)") (class "Default")
      (node (ref "R17") (pin "2") (pinfunction "2_2") (pintype "passive"))
      (node (ref "R26") (pin "1") (pinfunction "1_1") (pintype "passive"))
    )
    (net (code "123") (name "Net-(R20-Pad2)") (class "Default")
      (node (ref "R20") (pin "2") (pinfunction "2_2") (pintype "passive"))
      (node (ref "R21") (pin "1") (pinfunction "1_1") (pintype "passive"))
    )
    (net (code "124") (name "Net-(R21-Pad2)") (class "Default")
      (node (ref "R21") (pin "2") (pinfunction "2_2") (pintype "passive"))
      (node (ref "R22") (pin "1") (pinfunction "1_1") (pintype "passive"))
    )
    (net (code "125") (name "Net-(R22-Pad2)") (class "Default")
      (node (ref "R22") (pin "2") (pinfunction "2_2") (pintype "passive"))
      (node (ref "R23") (pin "1") (pinfunction "1_1") (pintype "passive"))
    )
    (net (code "126") (name "Net-(R25-Pad2)") (class "Default")
      (node (ref "R25") (pin "2") (pinfunction "2_2") (pintype "passive"))
      (node (ref "R37") (pin "1") (pinfunction "1_1") (pintype "passive"))
    )
    (net (code "127") (name "Net-(R26-Pad2)") (class "Default")
      (node (ref "R26") (pin "2") (pinfunction "2_2") (pintype "passive"))
      (node (ref "R38") (pin "1") (pinfunction "1_1") (pintype "passive"))
    )
    (net (code "128") (name "Net-(R27-Pad2)") (class "Default")
      (node (ref "R27") (pin "2") (pinfunction "2_2") (pintype "passive"))
      (node (ref "R28") (pin "1") (pinfunction "1_1") (pintype "passive"))
    )
    (net (code "129") (name "Net-(R28-Pad2)") (class "Default")
      (node (ref "R28") (pin "2") (pinfunction "2_2") (pintype "passive"))
      (node (ref "R29") (pin "1") (pinfunction "1_1") (pintype "passive"))
    )
    (net (code "130") (name "Net-(R29-Pad2)") (class "Default")
      (node (ref "R29") (pin "2") (pinfunction "2_2") (pintype "passive"))
      (node (ref "R30") (pin "1") (pinfunction "1_1") (pintype "passive"))
    )
    (net (code "131") (name "Net-(R31-Pad1)") (class "Default")
      (node (ref "R31") (pin "1") (pinfunction "1_1") (pintype "passive"))
      (node (ref "R32") (pin "2") (pinfunction "2_2") (pintype "passive"))
    )
    (net (code "132") (name "Net-(R32-Pad1)") (class "Default")
      (node (ref "R32") (pin "1") (pinfunction "1_1") (pintype "passive"))
      (node (ref "R33") (pin "2") (pinfunction "2_2") (pintype "passive"))
    )
    (net (code "133") (name "Net-(R33-Pad1)") (class "Default")
      (node (ref "R33") (pin "1") (pinfunction "1_1") (pintype "passive"))
      (node (ref "R34") (pin "2") (pinfunction "2_2") (pintype "passive"))
    )
    (net (code "134") (name "Net-(R40-Pad2)") (class "Default")
      (node (ref "R40") (pin "2") (pinfunction "2_2") (pintype "passive"))
      (node (ref "R41") (pin "1") (pinfunction "1_1") (pintype "passive"))
    )
    (net (code "135") (name "Net-(R41-Pad2)") (class "Default")
      (node (ref "R41") (pin "2") (pinfunction "2_2") (pintype "passive"))
      (node (ref "R42") (pin "1") (pinfunction "1_1") (pintype "passive"))
    )
    (net (code "136") (name "Net-(R42-Pad2)") (class "Default")
      (node (ref "R42") (pin "2") (pinfunction "2_2") (pintype "passive"))
      (node (ref "R43") (pin "1") (pinfunction "1_1") (pintype "passive"))
    )
    (net (code "137") (name "Net-(R45-Pad2)") (class "Default")
      (node (ref "R45") (pin "2") (pinfunction "2_2") (pintype "passive"))
      (node (ref "R49") (pin "1") (pinfunction "1_1") (pintype "passive"))
    )
    (net (code "138") (name "Net-(R46-Pad2)") (class "Default")
      (node (ref "R46") (pin "2") (pinfunction "2_2") (pintype "passive"))
      (node (ref "R50") (pin "1") (pinfunction "1_1") (pintype "passive"))
    )
    (net (code "139") (name "Net-(R49-Pad2)") (class "Default")
      (node (ref "R49") (pin "2") (pinfunction "2_2") (pintype "passive"))
      (node (ref "R54") (pin "1") (pinfunction "1_1") (pintype "passive"))
    )
    (net (code "140") (name "Net-(R50-Pad2)") (class "Default")
      (node (ref "R50") (pin "2") (pinfunction "2_2") (pintype "passive"))
      (node (ref "R55") (pin "1") (pinfunction "1_1") (pintype "passive"))
    )
    (net (code "141") (name "Net-(R52-Pad1)") (class "Default")
      (node (ref "R52") (pin "1") (pinfunction "1_1") (pintype "passive"))
      (node (ref "R56") (pin "2") (pinfunction "2_2") (pintype "passive"))
    )
    (net (code "142") (name "Net-(R54-Pad2)") (class "Default")
      (node (ref "R54") (pin "2") (pinfunction "2_2") (pintype "passive"))
      (node (ref "R57") (pin "1") (pinfunction "1_1") (pintype "passive"))
    )
    (net (code "143") (name "Net-(R55-Pad2)") (class "Default")
      (node (ref "R55") (pin "2") (pinfunction "2_2") (pintype "passive"))
      (node (ref "R58") (pin "1") (pinfunction "1_1") (pintype "passive"))
    )
    (net (code "144") (name "Net-(R56-Pad1)") (class "Default")
      (node (ref "R56") (pin "1") (pinfunction "1_1") (pintype "passive"))
      (node (ref "R59") (pin "2") (pinfunction "2_2") (pintype "passive"))
    )
    (net (code "145") (name "Net-(R57-Pad2)") (class "Default")
      (node (ref "R57") (pin "2") (pinfunction "2_2") (pintype "passive"))
      (node (ref "R60") (pin "1") (pinfunction "1_1") (pintype "passive"))
    )
    (net (code "146") (name "Net-(R64-Pad2)") (class "Default")
      (node (ref "R64") (pin "2") (pinfunction "2_2") (pintype "passive"))
      (node (ref "R69") (pin "2") (pinfunction "2_2") (pintype "passive"))
    )
    (net (code "147") (name "Net-(R70-Pad1)") (class "Default")
      (node (ref "R70") (pin "1") (pinfunction "1_1") (pintype "passive"))
      (node (ref "R73") (pin "2") (pinfunction "2_2") (pintype "passive"))
    )
    (net (code "148") (name "Net-(R71-Pad1)") (class "Default")
      (node (ref "R71") (pin "1") (pinfunction "1_1") (pintype "passive"))
      (node (ref "R74") (pin "2") (pinfunction "2_2") (pintype "passive"))
    )
    (net (code "149") (name "Net-(R71-Pad2)") (class "Default")
      (node (ref "R71") (pin "2") (pinfunction "2_2") (pintype "passive"))
      (node (ref "R73") (pin "1") (pinfunction "1_1") (pintype "passive"))
    )
    (net (code "150") (name "Net-(R72-Pad1)") (class "Default")
      (node (ref "R72") (pin "1") (pinfunction "1_1") (pintype "passive"))
      (node (ref "R75") (pin "2") (pinfunction "2_2") (pintype "passive"))
    )
    (net (code "151") (name "Net-(R72-Pad2)") (class "Default")
      (node (ref "R72") (pin "2") (pinfunction "2_2") (pintype "passive"))
      (node (ref "R74") (pin "1") (pinfunction "1_1") (pintype "passive"))
    )
    (net (code "152") (name "Net-(R78-Pad1)") (class "Default")
      (node (ref "R78") (pin "1") (pinfunction "1_1") (pintype "passive"))
      (node (ref "R81") (pin "2") (pinfunction "2_2") (pintype "passive"))
    )
    (net (code "153") (name "Net-(R81-Pad1)") (class "Default")
      (node (ref "R81") (pin "1") (pinfunction "1_1") (pintype "passive"))
      (node (ref "R86") (pin "2") (pinfunction "2_2") (pintype "passive"))
    )
    (net (code "154") (name "Net-(R82-Pad2)") (class "Default")
      (node (ref "R82") (pin "2") (pinfunction "2_2") (pintype "passive"))
      (node (ref "R83") (pin "1") (pinfunction "1_1") (pintype "passive"))
    )
    (net (code "155") (name "Net-(R100-Pad1)") (class "Default")
      (node (ref "R100") (pin "1") (pinfunction "1_1") (pintype "passive"))
      (node (ref "R101") (pin "2") (pinfunction "2_2") (pintype "passive"))
    )
    (net (code "156") (name "Net-(R104-Pad2)") (class "Default")
      (node (ref "R104") (pin "2") (pinfunction "2_2") (pintype "passive"))
      (node (ref "R105") (pin "2") (pinfunction "2_2") (pintype "passive"))
    )
    (net (code "157") (name "Net-(R110-Pad2)") (class "Default")
      (node (ref "R110") (pin "2") (pinfunction "2_2") (pintype "passive"))
      (node (ref "R111") (pin "1") (pinfunction "1_1") (pintype "passive"))
    )
    (net (code "158") (name "Net-(R114-Pad2)") (class "Default")
      (node (ref "R114") (pin "2") (pinfunction "2_2") (pintype "passive"))
      (node (ref "U8") (pin "1") (pinfunction "1_1") (pintype "passive"))
    )
    (net (code "159") (name "Net-(R122-Pad2)") (class "Default")
      (node (ref "R122") (pin "2") (pinfunction "2_2") (pintype "passive"))
      (node (ref "U8") (pin "4") (pinfunction "4_4") (pintype "passive"))
    )
    (net (code "160") (name "Net-(R131-Pad2)") (class "Default")
      (node (ref "R131") (pin "2") (pinfunction "2_2") (pintype "passive"))
      (node (ref "R137") (pin "2") (pinfunction "2_2") (pintype "passive"))
    )
    (net (code "161") (name "Net-(R132-Pad2)") (class "Default")
      (node (ref "R132") (pin "2") (pinfunction "2_2") (pintype "passive"))
      (node (ref "R133") (pin "2") (pinfunction "2_2") (pintype "passive"))
    )
    (net (code "162") (name "Net-(R133-Pad1)") (class "Default")
      (node (ref "R133") (pin "1") (pinfunction "1_1") (pintype "passive"))
      (node (ref "R134") (pin "1") (pinfunction "1_1") (pintype "passive"))
    )
    (net (code "163") (name "Net-(R134-Pad2)") (class "Default")
      (node (ref "R134") (pin "2") (pinfunction "2_2") (pintype "passive"))
      (node (ref "R135") (pin "2") (pinfunction "2_2") (pintype "passive"))
    )
    (net (code "164") (name "Net-(R137-Pad1)") (class "Default")
      (node (ref "R137") (pin "1") (pinfunction "1_1") (pintype "passive"))
      (node (ref "R138") (pin "1") (pinfunction "1_1") (pintype "passive"))
    )
    (net (code "165") (name "Net-(R138-Pad2)") (class "Default")
      (node (ref "R138") (pin "2") (pinfunction "2_2") (pintype "passive"))
      (node (ref "R144") (pin "2") (pinfunction "2_2") (pintype "passive"))
    )
    (net (code "166") (name "Net-(R139-Pad2)") (class "Default")
      (node (ref "R139") (pin "2") (pinfunction "2_2") (pintype "passive"))
      (node (ref "R140") (pin "2") (pinfunction "2_2") (pintype "passive"))
    )
    (net (code "167") (name "Net-(R140-Pad1)") (class "Default")
      (node (ref "R140") (pin "1") (pinfunction "1_1") (pintype "passive"))
      (node (ref "R141") (pin "1") (pinfunction "1_1") (pintype "passive"))
    )
    (net (code "168") (name "Net-(R141-Pad2)") (class "Default")
      (node (ref "R141") (pin "2") (pinfunction "2_2") (pintype "passive"))
      (node (ref "R142") (pin "2") (pinfunction "2_2") (pintype "passive"))
    )
    (net (code "169") (name "Net-(RV1-Pad2)") (class "Default")
      (node (ref "RV1") (pin "2") (pinfunction "2_2") (pintype "passive"))
      (node (ref "RV3") (pin "2") (pinfunction "2_2") (pintype "passive"))
      (node (ref "VR1") (pin "1") (pinfunction "1_1") (pintype "passive"))
    )
    (net (code "170") (name "Net-(U1-Vfef)") (class "Default")
      (node (ref "R4") (pin "2") (pinfunction "2_2") (pintype "passive"))
      (node (ref "U1") (pin "1") (pinfunction "Vfef_1") (pintype "passive"))
    )
    (net (code "171") (name "Net-(U1-Vout)") (class "Default")
      (node (ref "R3") (pin "2") (pinfunction "2_2") (pintype "passive"))
      (node (ref "U1") (pin "2") (pinfunction "Vout_2") (pintype "passive"))
    )
    (net (code "172") (name "Net-(U2-IN1)") (class "Default")
      (node (ref "R15") (pin "1") (pinfunction "1_1") (pintype "passive"))
      (node (ref "U2") (pin "1") (pinfunction "IN1_1") (pintype "passive"))
    )
    (net (code "173") (name "Net-(U2-IN2)") (class "Default")
      (node (ref "R19") (pin "1") (pinfunction "1_1") (pintype "passive"))
      (node (ref "U2") (pin "2") (pinfunction "IN2_2") (pintype "passive"))
    )
    (net (code "174") (name "Net-(U2-IN3)") (class "Default")
      (node (ref "R24") (pin "1") (pinfunction "1_1") (pintype "passive"))
      (node (ref "U2") (pin "3") (pinfunction "IN3_3") (pintype "passive"))
    )
    (net (code "175") (name "Net-(U2-IN4)") (class "Default")
      (node (ref "R36") (pin "1") (pinfunction "1_1") (pintype "passive"))
      (node (ref "U2") (pin "4") (pinfunction "IN4_4") (pintype "passive"))
    )
    (net (code "176") (name "Net-(U2-IN5)") (class "Default")
      (node (ref "R39") (pin "1") (pinfunction "1_1") (pintype "passive"))
      (node (ref "U2") (pin "5") (pinfunction "IN5_5") (pintype "passive"))
    )
    (net (code "177") (name "Net-(U2-IN6)") (class "Default")
      (node (ref "R47") (pin "1") (pinfunction "1_1") (pintype "passive"))
      (node (ref "U2") (pin "6") (pinfunction "IN6_6") (pintype "passive"))
    )
    (net (code "178") (name "Net-(U2-IN7)") (class "Default")
      (node (ref "R51") (pin "1") (pinfunction "1_1") (pintype "passive"))
      (node (ref "U2") (pin "7") (pinfunction "IN7_7") (pintype "passive"))
    )
    (net (code "179") (name "Net-(U4A-1_IN-)") (class "Default")
      (node (ref "U4") (pin "1") (pinfunction "1_OUT_1") (pintype "output"))
      (node (ref "U4") (pin "2") (pinfunction "1_IN-_2") (pintype "input"))
    )
    (net (code "180") (name "Net-(U4B-2_IN+)") (class "Default")
      (node (ref "C78") (pin "1") (pinfunction "1_1") (pintype "passive"))
      (node (ref "R111") (pin "2") (pinfunction "2_2") (pintype "passive"))
      (node (ref "R121") (pin "1") (pinfunction "1_1") (pintype "passive"))
      (node (ref "U4") (pin "5") (pinfunction "2_IN+_5") (pintype "input"))
    )
    (net (code "181") (name "Net-(U4B-2_IN-)") (class "Default")
      (node (ref "C71") (pin "2") (pinfunction "2_2") (pintype "passive"))
      (node (ref "R105") (pin "1") (pinfunction "1_1") (pintype "passive"))
      (node (ref "R99") (pin "2") (pinfunction "2_2") (pintype "passive"))
      (node (ref "U4") (pin "6") (pinfunction "2_IN-_6") (pintype "input"))
    )
    (net (code "182") (name "Net-(U4B-2_OUT)") (class "Default")
      (node (ref "C71") (pin "1") (pinfunction "1_1") (pintype "passive"))
      (node (ref "R107") (pin "2") (pinfunction "2_2") (pintype "passive"))
      (node (ref "R99") (pin "1") (pinfunction "1_1") (pintype "passive"))
      (node (ref "U4") (pin "7") (pinfunction "2_OUT_7") (pintype "output"))
    )
    (net (code "183") (name "Net-(U4C-3_IN-)") (class "Default")
      (node (ref "U4") (pin "8") (pinfunction "3_OUT_8") (pintype "output"))
      (node (ref "U4") (pin "9") (pinfunction "3_IN-_9") (pintype "input"))
    )
    (net (code "184") (name "Net-(U4D-4_IN-)") (class "Default")
      (node (ref "U4") (pin "13") (pinfunction "4_IN-_13") (pintype "input"))
      (node (ref "U4") (pin "14") (pinfunction "4_OUT_14") (pintype "output"))
    )
    (net (code "185") (name "Net-(U6-BBA)") (class "Default")
      (node (ref "C61") (pin "2") (pinfunction "2_2") (pintype "passive"))
      (node (ref "R86") (pin "1") (pinfunction "1_1") (pintype "passive"))
      (node (ref "R97") (pin "2") (pinfunction "2_2") (pintype "passive"))
      (node (ref "U6") (pin "1") (pinfunction "BBA_1") (pintype "passive"))
    )
    (net (code "186") (name "Net-(U6-CS)") (class "Default")
      (node (ref "R93") (pin "1") (pinfunction "1_1") (pintype "passive"))
      (node (ref "R94") (pin "1") (pinfunction "1_1") (pintype "passive"))
      (node (ref "U6") (pin "3") (pinfunction "CS_3") (pintype "passive"))
    )
    (net (code "187") (name "Net-(U6-FBB)") (class "Default")
      (node (ref "C81") (pin "2") (pinfunction "2_2") (pintype "passive"))
      (node (ref "R122") (pin "1") (pinfunction "1_1") (pintype "passive"))
      (node (ref "U6") (pin "2") (pinfunction "FBB_2") (pintype "passive"))
    )
    (net (code "188") (name "Net-(U6-VCC)") (class "Default")
      (node (ref "C59") (pin "1") (pinfunction "1_1") (pintype "passive"))
      (node (ref "C62") (pin "1") (pinfunction "1_1") (pintype "passive"))
      (node (ref "C63") (pin "1") (pinfunction "1_1") (pintype "passive"))
      (node (ref "R89") (pin "2") (pinfunction "2_2") (pintype "passive"))
      (node (ref "U6") (pin "7") (pinfunction "VCC_7") (pintype "power_in"))
    )
    (net (code "189") (name "Net-(U7-CURRENT_SENSE)") (class "Default")
      (node (ref "C77") (pin "2") (pinfunction "2_2") (pintype "passive"))
      (node (ref "C84") (pin "1") (pinfunction "1_1") (pintype "passive"))
      (node (ref "R109") (pin "2") (pinfunction "2_2") (pintype "passive"))
      (node (ref "U7") (pin "3") (pinfunction "CURRENT_SENSE_3") (pintype "input"))
    )
    (net (code "190") (name "Net-(U7-OUT)") (class "Default")
      (node (ref "D22") (pin "1") (pinfunction "C_1") (pintype "passive"))
      (node (ref "D22") (pin "2") (pinfunction "C_2") (pintype "passive"))
      (node (ref "R103") (pin "2") (pinfunction "2_2") (pintype "passive"))
      (node (ref "U7") (pin "6") (pinfunction "OUT_6") (pintype "output"))
    )
    (net (code "191") (name "Net-(U7-RT{slash}CT)") (class "Default")
      (node (ref "C80") (pin "2") (pinfunction "2_2") (pintype "passive"))
      (node (ref "C84") (pin "2") (pinfunction "2_2") (pintype "passive"))
      (node (ref "R112") (pin "1") (pinfunction "1_1") (pintype "passive"))
      (node (ref "U7") (pin "4") (pinfunction "RT/CT_4") (pintype "input"))
    )
    (net (code "192") (name "Net-(U7-VCC)") (class "Default")
      (node (ref "C66") (pin "1") (pinfunction "1_1") (pintype "passive"))
      (node (ref "C73") (pin "2") (pinfunction "2_2") (pintype "passive"))
      (node (ref "H7") (pin "1") (pinfunction "1_1") (pintype "passive"))
      (node (ref "R95") (pin "2") (pinfunction "2_2") (pintype "passive"))
      (node (ref "U7") (pin "7") (pinfunction "VCC_7") (pintype "power_in"))
    )
    (net (code "193") (name "Net-(U7-VOLTAGE_FB)") (class "Default")
      (node (ref "C74") (pin "2") (pinfunction "2_2") (pintype "passive"))
      (node (ref "R116") (pin "1") (pinfunction "1_1") (pintype "passive"))
      (node (ref "U7") (pin "2") (pinfunction "VOLTAGE_FB_2") (pintype "input"))
    )
    (net (code "194") (name "Net-(U7-VREF)") (class "Default")
      (node (ref "C79") (pin "2") (pinfunction "2_2") (pintype "passive"))
      (node (ref "D25") (pin "2") (pinfunction "C_2") (pintype "passive"))
      (node (ref "R112") (pin "2") (pinfunction "2_2") (pintype "passive"))
      (node (ref "R136") (pin "1") (pinfunction "1_1") (pintype "passive"))
      (node (ref "U7") (pin "8") (pinfunction "VREF_8") (pintype "output"))
    )
    (net (code "195") (name "Net-(U9-K)") (class "Default")
      (node (ref "C83") (pin "1") (pinfunction "1_1") (pintype "passive"))
      (node (ref "R123") (pin "2") (pinfunction "2_2") (pintype "passive"))
      (node (ref "R126") (pin "1") (pinfunction "1_1") (pintype "passive"))
      (node (ref "U8") (pin "2") (pinfunction "2_2") (pintype "passive"))
      (node (ref "U9") (pin "1") (pinfunction "K_1") (pintype "passive"))
    )
    (net (code "196") (name "Net-(U9-R)") (class "Default")
      (node (ref "C85") (pin "2") (pinfunction "2_2") (pintype "passive"))
      (node (ref "R101") (pin "1") (pinfunction "1_1") (pintype "passive"))
      (node (ref "R128") (pin "2") (pinfunction "2_2") (pintype "passive"))
      (node (ref "R129") (pin "2") (pinfunction "2_2") (pintype "passive"))
      (node (ref "R98") (pin "2") (pinfunction "2_2") (pintype "passive"))
      (node (ref "U9") (pin "8") (pinfunction "R_8") (pintype "passive"))
    )
    (net (code "197") (name "Net-(U10-Vfef)") (class "Default")
      (node (ref "R104") (pin "1") (pinfunction "1_1") (pintype "passive"))
      (node (ref "U10") (pin "1") (pinfunction "Vfef_1") (pintype "passive"))
    )
    (net (code "198") (name "Net-(U10-Vout)") (class "Default")
      (node (ref "R110") (pin "1") (pinfunction "1_1") (pintype "passive"))
      (node (ref "U10") (pin "2") (pinfunction "Vout_2") (pintype "passive"))
    )
    (net (code "199") (name "unconnected-(D9-A-Pad1)") (class "Default")
      (node (ref "D9") (pin "1") (pinfunction "A_1") (pintype "passive+no_connect"))
    )
    (net (code "200") (name "unconnected-(D20-NC-Pad2)") (class "Default")
      (node (ref "D20") (pin "2") (pinfunction "NC_2") (pintype "passive+no_connect"))
    )
    (net (code "201") (name "unconnected-(D23-NC-Pad2)") (class "Default")
      (node (ref "D23") (pin "2") (pinfunction "NC_2") (pintype "passive+no_connect"))
    )
    (net (code "202") (name "unconnected-(D24-NC-Pad2)") (class "Default")
      (node (ref "D24") (pin "2") (pinfunction "NC_2") (pintype "passive+no_connect"))
    )
    (net (code "203") (name "unconnected-(H8-Pad3)") (class "Default")
      (node (ref "H8") (pin "3") (pinfunction "3_3") (pintype "passive"))
    )
    (net (code "204") (name "unconnected-(H8-Pad20)") (class "Default")
      (node (ref "H8") (pin "20") (pinfunction "20_20") (pintype "passive+no_connect"))
    )
    (net (code "205") (name "unconnected-(H8-Pad21)") (class "Default")
      (node (ref "H8") (pin "21") (pinfunction "21_21") (pintype "passive+no_connect"))
    )
    (net (code "206") (name "unconnected-(H8-Pad29)") (class "Default")
      (node (ref "H8") (pin "29") (pinfunction "29_29") (pintype "passive+no_connect"))
    )
    (net (code "207") (name "unconnected-(H8-Pad30)") (class "Default")
      (node (ref "H8") (pin "30") (pinfunction "30_30") (pintype "passive+no_connect"))
    )
    (net (code "208") (name "unconnected-(K3-Pad3)") (class "Default")
      (node (ref "K3") (pin "3") (pinfunction "3_3") (pintype "passive+no_connect"))
    )
    (net (code "209") (name "unconnected-(K3-Pad10)") (class "Default")
      (node (ref "K3") (pin "10") (pinfunction "10_10") (pintype "passive+no_connect"))
    )
    (net (code "210") (name "unconnected-(U6-NC-Pad4)") (class "Default")
      (node (ref "U6") (pin "4") (pinfunction "NC_4") (pintype "passive+no_connect"))
    )
    (net (code "211") (name "unconnected-(U9-NC-Pad4)") (class "Default")
      (node (ref "U9") (pin "4") (pinfunction "NC_4") (pintype "passive"))
    )
    (net (code "212") (name "unconnected-(U9-NC-Pad5)") (class "Default")
      (node (ref "U9") (pin "5") (pinfunction "NC_5") (pintype "passive"))
    )
  )
)
